# axiom_beta_interface_dummy_v0_13_r1_3.net
KiCad netlist of a schematic drawn in EAGLE
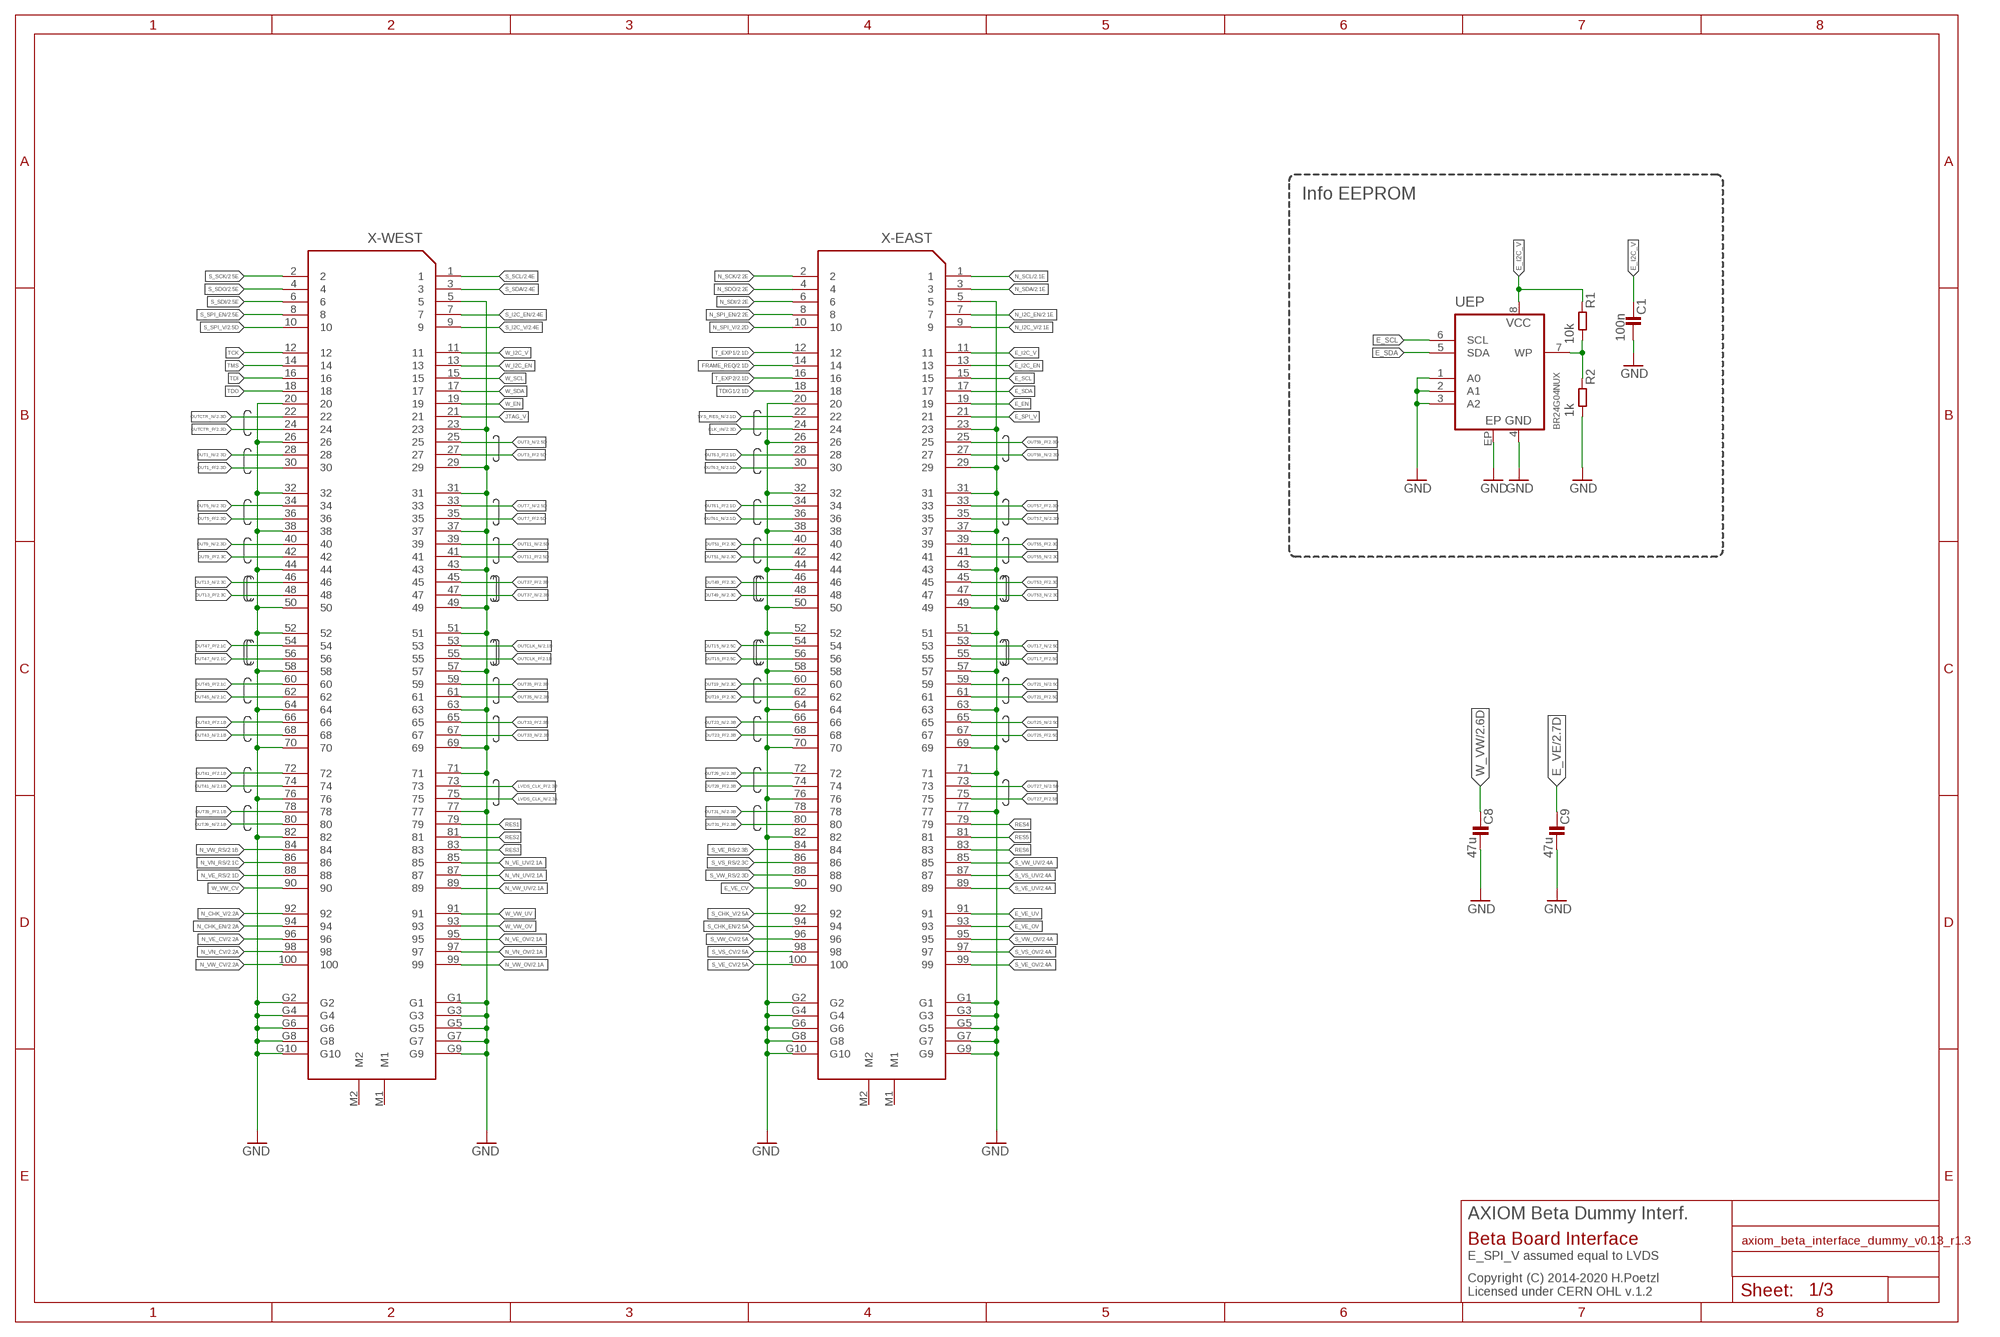
[diagram p0: schematic, sheet 1]
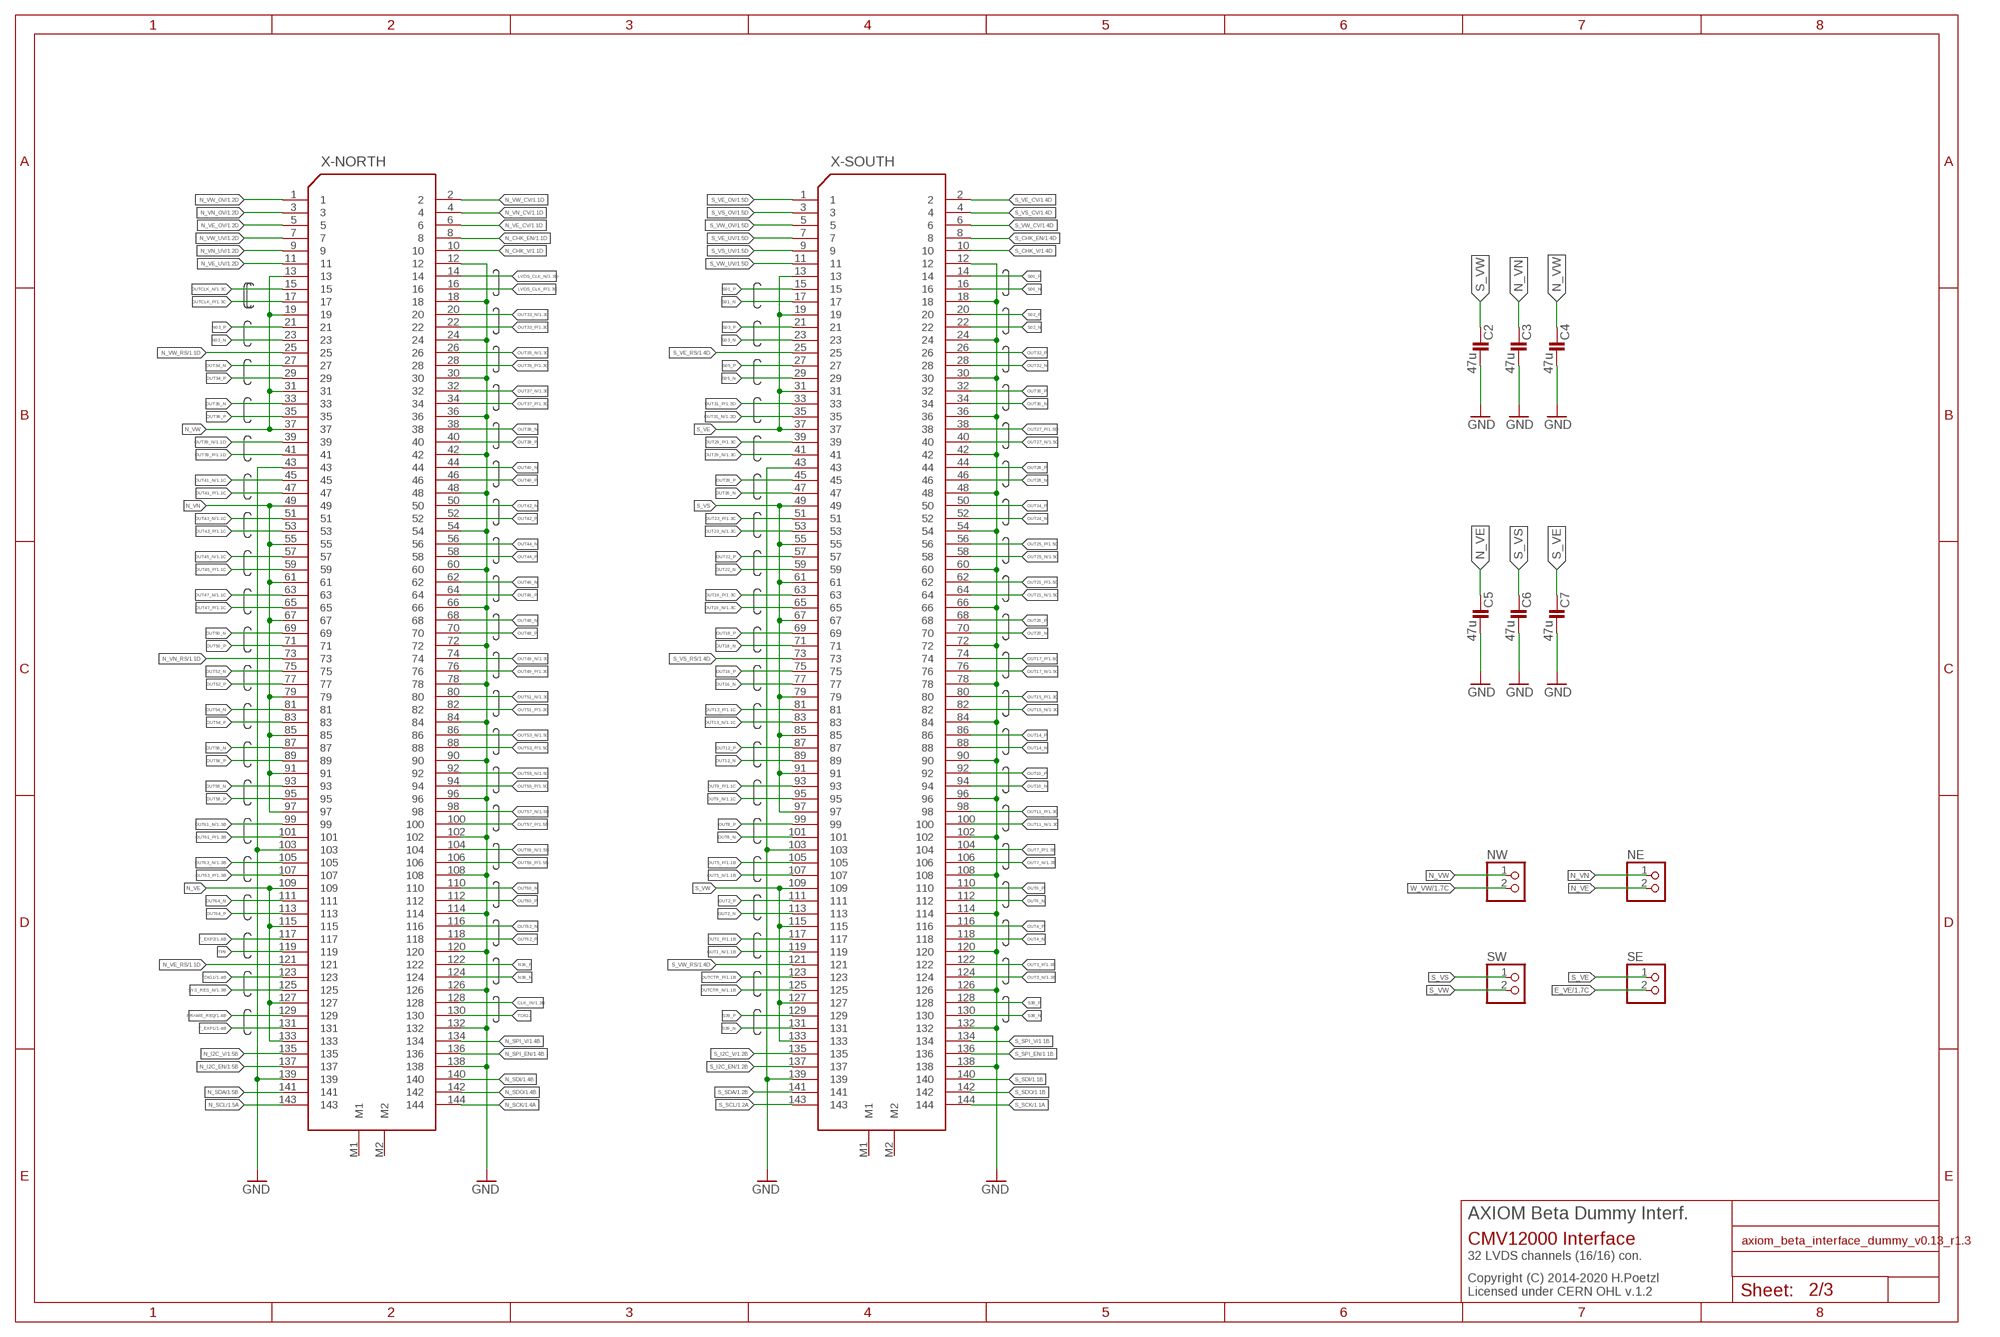
[diagram p1: schematic, sheet 2]
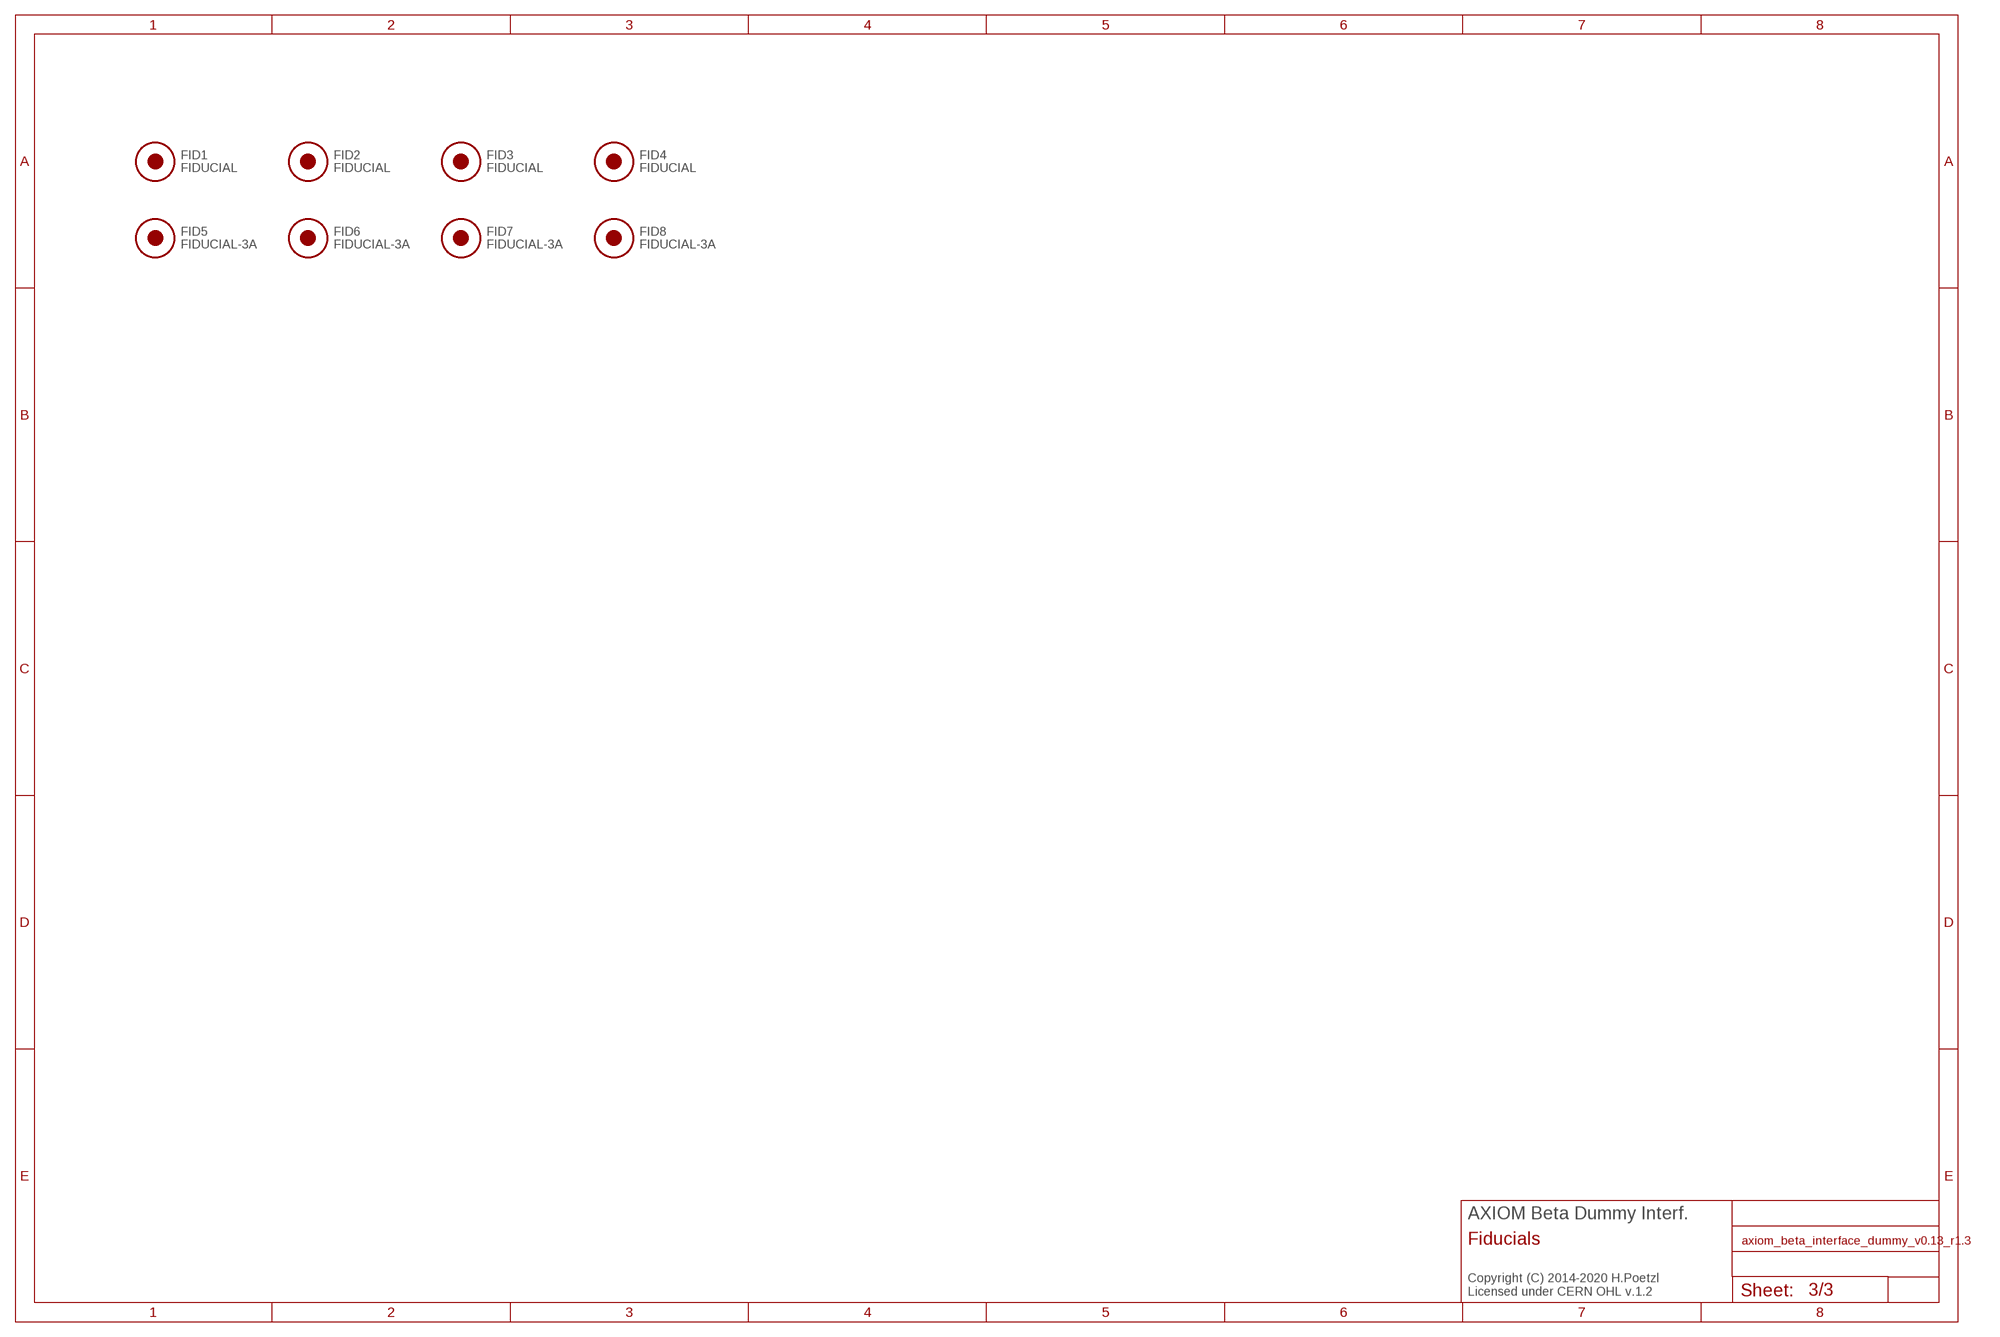
[diagram p2: schematic, sheet 3]

(export (version "E")
  (design (tool "Eeschema 10.0.6"))
  (components
    (comp (ref "FID1")
      (value "FIDUCIAL")
      (footprint "eagle-import:FID_ARROW")
      (libsource (lib "eagle-import") (part "FIDUCIAL"))
    )
    (comp (ref "FID2")
      (value "FIDUCIAL")
      (footprint "eagle-import:FID_ARROW")
      (libsource (lib "eagle-import") (part "FIDUCIAL"))
    )
    (comp (ref "FID3")
      (value "FIDUCIAL")
      (footprint "eagle-import:FID_ARROW")
      (libsource (lib "eagle-import") (part "FIDUCIAL"))
    )
    (comp (ref "FID4")
      (value "FIDUCIAL")
      (footprint "eagle-import:FID_ARROW")
      (libsource (lib "eagle-import") (part "FIDUCIAL"))
    )
    (comp (ref "FID5")
      (value "FIDUCIAL-3A")
      (footprint "eagle-import:FID_3ARROW")
      (libsource (lib "eagle-import") (part "FIDUCIAL-3A"))
    )
    (comp (ref "FID6")
      (value "FIDUCIAL-3A")
      (footprint "eagle-import:FID_3ARROW")
      (libsource (lib "eagle-import") (part "FIDUCIAL-3A"))
    )
    (comp (ref "FID7")
      (value "FIDUCIAL-3A")
      (footprint "eagle-import:FID_3ARROW")
      (libsource (lib "eagle-import") (part "FIDUCIAL-3A"))
    )
    (comp (ref "FID8")
      (value "FIDUCIAL-3A")
      (footprint "eagle-import:FID_3ARROW")
      (libsource (lib "eagle-import") (part "FIDUCIAL-3A"))
    )
    (comp (ref "C1")
      (value "100n")
      (footprint "eagle-import:0402-B")
      (libsource (lib "eagle-import") (part "C0402-B"))
    )
    (comp (ref "C8")
      (value "47u")
      (footprint "eagle-import:0805-B")
      (libsource (lib "eagle-import") (part "C0805-B"))
    )
    (comp (ref "C9")
      (value "47u")
      (footprint "eagle-import:0805-B")
      (libsource (lib "eagle-import") (part "C0805-B"))
    )
    (comp (ref "R1")
      (value "10k")
      (footprint "eagle-import:0402-B")
      (libsource (lib "eagle-import") (part "R0402-B"))
    )
    (comp (ref "R2")
      (value "1k")
      (footprint "eagle-import:0402-B")
      (libsource (lib "eagle-import") (part "R0402-B"))
    )
    (comp (ref "UEP")
      (value "BR24G04NUX")
      (footprint "eagle-import:DFN200X300X100-9N")
      (libsource (lib "eagle-import") (part "BR24G04NUX"))
    )
    (comp (ref "X-EAST")
      (value "FX10-100/10P")
      (footprint "eagle-import:FX10A-100P_10")
      (libsource (lib "eagle-import") (part "FX10-100/10P"))
    )
    (comp (ref "X-WEST")
      (value "FX10-100/10P")
      (footprint "eagle-import:FX10A-100P_10")
      (libsource (lib "eagle-import") (part "FX10-100/10P"))
    )
    (comp (ref "C2")
      (value "47u")
      (footprint "eagle-import:0805-B")
      (libsource (lib "eagle-import") (part "C0805-B"))
    )
    (comp (ref "C3")
      (value "47u")
      (footprint "eagle-import:0805-B")
      (libsource (lib "eagle-import") (part "C0805-B"))
    )
    (comp (ref "C4")
      (value "47u")
      (footprint "eagle-import:0805-B")
      (libsource (lib "eagle-import") (part "C0805-B"))
    )
    (comp (ref "C5")
      (value "47u")
      (footprint "eagle-import:0805-B")
      (libsource (lib "eagle-import") (part "C0805-B"))
    )
    (comp (ref "C6")
      (value "47u")
      (footprint "eagle-import:0805-B")
      (libsource (lib "eagle-import") (part "C0805-B"))
    )
    (comp (ref "C7")
      (value "47u")
      (footprint "eagle-import:0805-B")
      (libsource (lib "eagle-import") (part "C0805-B"))
    )
    (comp (ref "NE")
      (value "PINHD-1X02_2.54")
      (footprint "eagle-import:1X02")
      (libsource (lib "eagle-import") (part "PINHD-1X02_2.54"))
    )
    (comp (ref "NW")
      (value "PINHD-1X02_2.54")
      (footprint "eagle-import:1X02")
      (libsource (lib "eagle-import") (part "PINHD-1X02_2.54"))
    )
    (comp (ref "SE")
      (value "PINHD-1X02_2.54")
      (footprint "eagle-import:1X02")
      (libsource (lib "eagle-import") (part "PINHD-1X02_2.54"))
    )
    (comp (ref "SW")
      (value "PINHD-1X02_2.54")
      (footprint "eagle-import:1X02")
      (libsource (lib "eagle-import") (part "PINHD-1X02_2.54"))
    )
    (comp (ref "X-NORTH")
      (value "FX10-144S")
      (footprint "eagle-import:FX10A-144S")
      (libsource (lib "eagle-import") (part "FX10-144S"))
    )
    (comp (ref "X-SOUTH")
      (value "FX10-144S")
      (footprint "eagle-import:FX10A-144S")
      (libsource (lib "eagle-import") (part "FX10-144S"))
    )
  )
  (nets
    (net (code "1") (name "CLK_IN") (class "Default")
      (node (ref "X-EAST") (pin "24") (pinfunction "24_24") (pintype "bidirectional"))
      (node (ref "X-NORTH") (pin "128") (pinfunction "128_128") (pintype "bidirectional"))
    )
    (net (code "2") (name "E_EN") (class "Default")
      (node (ref "X-EAST") (pin "19") (pinfunction "19_19") (pintype "bidirectional"))
    )
    (net (code "3") (name "E_I2C_EN") (class "Default")
      (node (ref "X-EAST") (pin "13") (pinfunction "13_13") (pintype "bidirectional"))
    )
    (net (code "4") (name "E_I2C_V") (class "Default")
      (node (ref "C1") (pin "1") (pinfunction "1_1") (pintype "passive"))
      (node (ref "R1") (pin "1") (pinfunction "1_1") (pintype "passive"))
      (node (ref "UEP") (pin "8") (pinfunction "VCC_8") (pintype "power_in"))
      (node (ref "X-EAST") (pin "11") (pinfunction "11_11") (pintype "bidirectional"))
    )
    (net (code "5") (name "E_SCL") (class "Default")
      (node (ref "UEP") (pin "6") (pinfunction "SCL_6") (pintype "input"))
      (node (ref "X-EAST") (pin "15") (pinfunction "15_15") (pintype "bidirectional"))
    )
    (net (code "6") (name "E_SDA") (class "Default")
      (node (ref "UEP") (pin "5") (pinfunction "SDA_5") (pintype "bidirectional"))
      (node (ref "X-EAST") (pin "17") (pinfunction "17_17") (pintype "bidirectional"))
    )
    (net (code "7") (name "E_SPI_V") (class "Default")
      (node (ref "X-EAST") (pin "21") (pinfunction "21_21") (pintype "bidirectional"))
    )
    (net (code "8") (name "E_VE") (class "Default")
      (node (ref "C9") (pin "1") (pinfunction "1_1") (pintype "passive"))
      (node (ref "SE") (pin "2") (pinfunction "2_2") (pintype "passive"))
    )
    (net (code "9") (name "E_VE_CV") (class "Default")
      (node (ref "X-EAST") (pin "90") (pinfunction "90_90") (pintype "bidirectional"))
    )
    (net (code "10") (name "E_VE_OV") (class "Default")
      (node (ref "X-EAST") (pin "93") (pinfunction "93_93") (pintype "bidirectional"))
    )
    (net (code "11") (name "E_VE_UV") (class "Default")
      (node (ref "X-EAST") (pin "91") (pinfunction "91_91") (pintype "bidirectional"))
    )
    (net (code "12") (name "FRAME_REQ") (class "Default")
      (node (ref "X-EAST") (pin "14") (pinfunction "14_14") (pintype "bidirectional"))
      (node (ref "X-NORTH") (pin "129") (pinfunction "129_129") (pintype "bidirectional"))
    )
    (net (code "13") (name "GND") (class "Default")
      (node (ref "C1") (pin "2") (pinfunction "2_2") (pintype "passive"))
      (node (ref "C2") (pin "2") (pinfunction "2_2") (pintype "passive"))
      (node (ref "C3") (pin "2") (pinfunction "2_2") (pintype "passive"))
      (node (ref "C4") (pin "2") (pinfunction "2_2") (pintype "passive"))
      (node (ref "C5") (pin "2") (pinfunction "2_2") (pintype "passive"))
      (node (ref "C6") (pin "2") (pinfunction "2_2") (pintype "passive"))
      (node (ref "C7") (pin "2") (pinfunction "2_2") (pintype "passive"))
      (node (ref "C8") (pin "2") (pinfunction "2_2") (pintype "passive"))
      (node (ref "C9") (pin "2") (pinfunction "2_2") (pintype "passive"))
      (node (ref "R2") (pin "2") (pinfunction "2_2") (pintype "passive"))
      (node (ref "UEP") (pin "1") (pinfunction "A0_1") (pintype "input"))
      (node (ref "UEP") (pin "2") (pinfunction "A1_2") (pintype "input"))
      (node (ref "UEP") (pin "3") (pinfunction "A2_3") (pintype "input"))
      (node (ref "UEP") (pin "4") (pinfunction "GND_4") (pintype "passive"))
      (node (ref "UEP") (pin "EP") (pinfunction "EP_EP") (pintype "passive"))
      (node (ref "X-EAST") (pin "20") (pinfunction "20_20") (pintype "bidirectional"))
      (node (ref "X-EAST") (pin "23") (pinfunction "23_23") (pintype "bidirectional"))
      (node (ref "X-EAST") (pin "26") (pinfunction "26_26") (pintype "bidirectional"))
      (node (ref "X-EAST") (pin "29") (pinfunction "29_29") (pintype "bidirectional"))
      (node (ref "X-EAST") (pin "31") (pinfunction "31_31") (pintype "bidirectional"))
      (node (ref "X-EAST") (pin "32") (pinfunction "32_32") (pintype "bidirectional"))
      (node (ref "X-EAST") (pin "37") (pinfunction "37_37") (pintype "bidirectional"))
      (node (ref "X-EAST") (pin "38") (pinfunction "38_38") (pintype "bidirectional"))
      (node (ref "X-EAST") (pin "43") (pinfunction "43_43") (pintype "bidirectional"))
      (node (ref "X-EAST") (pin "44") (pinfunction "44_44") (pintype "bidirectional"))
      (node (ref "X-EAST") (pin "49") (pinfunction "49_49") (pintype "bidirectional"))
      (node (ref "X-EAST") (pin "5") (pinfunction "5_5") (pintype "bidirectional"))
      (node (ref "X-EAST") (pin "50") (pinfunction "50_50") (pintype "bidirectional"))
      (node (ref "X-EAST") (pin "51") (pinfunction "51_51") (pintype "bidirectional"))
      (node (ref "X-EAST") (pin "52") (pinfunction "52_52") (pintype "bidirectional"))
      (node (ref "X-EAST") (pin "57") (pinfunction "57_57") (pintype "bidirectional"))
      (node (ref "X-EAST") (pin "58") (pinfunction "58_58") (pintype "bidirectional"))
      (node (ref "X-EAST") (pin "63") (pinfunction "63_63") (pintype "bidirectional"))
      (node (ref "X-EAST") (pin "64") (pinfunction "64_64") (pintype "bidirectional"))
      (node (ref "X-EAST") (pin "69") (pinfunction "69_69") (pintype "bidirectional"))
      (node (ref "X-EAST") (pin "70") (pinfunction "70_70") (pintype "bidirectional"))
      (node (ref "X-EAST") (pin "71") (pinfunction "71_71") (pintype "bidirectional"))
      (node (ref "X-EAST") (pin "76") (pinfunction "76_76") (pintype "bidirectional"))
      (node (ref "X-EAST") (pin "77") (pinfunction "77_77") (pintype "bidirectional"))
      (node (ref "X-EAST") (pin "82") (pinfunction "82_82") (pintype "bidirectional"))
      (node (ref "X-EAST") (pin "G1") (pinfunction "G1_G1") (pintype "bidirectional"))
      (node (ref "X-EAST") (pin "G10") (pinfunction "G10_G10") (pintype "bidirectional"))
      (node (ref "X-EAST") (pin "G2") (pinfunction "G2_G2") (pintype "bidirectional"))
      (node (ref "X-EAST") (pin "G3") (pinfunction "G3_G3") (pintype "bidirectional"))
      (node (ref "X-EAST") (pin "G4") (pinfunction "G4_G4") (pintype "bidirectional"))
      (node (ref "X-EAST") (pin "G5") (pinfunction "G5_G5") (pintype "bidirectional"))
      (node (ref "X-EAST") (pin "G6") (pinfunction "G6_G6") (pintype "bidirectional"))
      (node (ref "X-EAST") (pin "G7") (pinfunction "G7_G7") (pintype "bidirectional"))
      (node (ref "X-EAST") (pin "G8") (pinfunction "G8_G8") (pintype "bidirectional"))
      (node (ref "X-EAST") (pin "G9") (pinfunction "G9_G9") (pintype "bidirectional"))
      (node (ref "X-NORTH") (pin "102") (pinfunction "102_102") (pintype "bidirectional"))
      (node (ref "X-NORTH") (pin "103") (pinfunction "103_103") (pintype "bidirectional"))
      (node (ref "X-NORTH") (pin "108") (pinfunction "108_108") (pintype "bidirectional"))
      (node (ref "X-NORTH") (pin "114") (pinfunction "114_114") (pintype "bidirectional"))
      (node (ref "X-NORTH") (pin "12") (pinfunction "12_12") (pintype "bidirectional"))
      (node (ref "X-NORTH") (pin "120") (pinfunction "120_120") (pintype "bidirectional"))
      (node (ref "X-NORTH") (pin "126") (pinfunction "126_126") (pintype "bidirectional"))
      (node (ref "X-NORTH") (pin "132") (pinfunction "132_132") (pintype "bidirectional"))
      (node (ref "X-NORTH") (pin "138") (pinfunction "138_138") (pintype "bidirectional"))
      (node (ref "X-NORTH") (pin "139") (pinfunction "139_139") (pintype "bidirectional"))
      (node (ref "X-NORTH") (pin "18") (pinfunction "18_18") (pintype "bidirectional"))
      (node (ref "X-NORTH") (pin "24") (pinfunction "24_24") (pintype "bidirectional"))
      (node (ref "X-NORTH") (pin "30") (pinfunction "30_30") (pintype "bidirectional"))
      (node (ref "X-NORTH") (pin "36") (pinfunction "36_36") (pintype "bidirectional"))
      (node (ref "X-NORTH") (pin "42") (pinfunction "42_42") (pintype "bidirectional"))
      (node (ref "X-NORTH") (pin "43") (pinfunction "43_43") (pintype "bidirectional"))
      (node (ref "X-NORTH") (pin "48") (pinfunction "48_48") (pintype "bidirectional"))
      (node (ref "X-NORTH") (pin "54") (pinfunction "54_54") (pintype "bidirectional"))
      (node (ref "X-NORTH") (pin "60") (pinfunction "60_60") (pintype "bidirectional"))
      (node (ref "X-NORTH") (pin "66") (pinfunction "66_66") (pintype "bidirectional"))
      (node (ref "X-NORTH") (pin "72") (pinfunction "72_72") (pintype "bidirectional"))
      (node (ref "X-NORTH") (pin "78") (pinfunction "78_78") (pintype "bidirectional"))
      (node (ref "X-NORTH") (pin "84") (pinfunction "84_84") (pintype "bidirectional"))
      (node (ref "X-NORTH") (pin "90") (pinfunction "90_90") (pintype "bidirectional"))
      (node (ref "X-NORTH") (pin "96") (pinfunction "96_96") (pintype "bidirectional"))
      (node (ref "X-SOUTH") (pin "102") (pinfunction "102_102") (pintype "bidirectional"))
      (node (ref "X-SOUTH") (pin "103") (pinfunction "103_103") (pintype "bidirectional"))
      (node (ref "X-SOUTH") (pin "108") (pinfunction "108_108") (pintype "bidirectional"))
      (node (ref "X-SOUTH") (pin "114") (pinfunction "114_114") (pintype "bidirectional"))
      (node (ref "X-SOUTH") (pin "12") (pinfunction "12_12") (pintype "bidirectional"))
      (node (ref "X-SOUTH") (pin "120") (pinfunction "120_120") (pintype "bidirectional"))
      (node (ref "X-SOUTH") (pin "126") (pinfunction "126_126") (pintype "bidirectional"))
      (node (ref "X-SOUTH") (pin "132") (pinfunction "132_132") (pintype "bidirectional"))
      (node (ref "X-SOUTH") (pin "138") (pinfunction "138_138") (pintype "bidirectional"))
      (node (ref "X-SOUTH") (pin "139") (pinfunction "139_139") (pintype "bidirectional"))
      (node (ref "X-SOUTH") (pin "18") (pinfunction "18_18") (pintype "bidirectional"))
      (node (ref "X-SOUTH") (pin "24") (pinfunction "24_24") (pintype "bidirectional"))
      (node (ref "X-SOUTH") (pin "30") (pinfunction "30_30") (pintype "bidirectional"))
      (node (ref "X-SOUTH") (pin "36") (pinfunction "36_36") (pintype "bidirectional"))
      (node (ref "X-SOUTH") (pin "42") (pinfunction "42_42") (pintype "bidirectional"))
      (node (ref "X-SOUTH") (pin "43") (pinfunction "43_43") (pintype "bidirectional"))
      (node (ref "X-SOUTH") (pin "48") (pinfunction "48_48") (pintype "bidirectional"))
      (node (ref "X-SOUTH") (pin "54") (pinfunction "54_54") (pintype "bidirectional"))
      (node (ref "X-SOUTH") (pin "60") (pinfunction "60_60") (pintype "bidirectional"))
      (node (ref "X-SOUTH") (pin "66") (pinfunction "66_66") (pintype "bidirectional"))
      (node (ref "X-SOUTH") (pin "72") (pinfunction "72_72") (pintype "bidirectional"))
      (node (ref "X-SOUTH") (pin "78") (pinfunction "78_78") (pintype "bidirectional"))
      (node (ref "X-SOUTH") (pin "84") (pinfunction "84_84") (pintype "bidirectional"))
      (node (ref "X-SOUTH") (pin "90") (pinfunction "90_90") (pintype "bidirectional"))
      (node (ref "X-SOUTH") (pin "96") (pinfunction "96_96") (pintype "bidirectional"))
      (node (ref "X-WEST") (pin "20") (pinfunction "20_20") (pintype "bidirectional"))
      (node (ref "X-WEST") (pin "23") (pinfunction "23_23") (pintype "bidirectional"))
      (node (ref "X-WEST") (pin "26") (pinfunction "26_26") (pintype "bidirectional"))
      (node (ref "X-WEST") (pin "29") (pinfunction "29_29") (pintype "bidirectional"))
      (node (ref "X-WEST") (pin "31") (pinfunction "31_31") (pintype "bidirectional"))
      (node (ref "X-WEST") (pin "32") (pinfunction "32_32") (pintype "bidirectional"))
      (node (ref "X-WEST") (pin "37") (pinfunction "37_37") (pintype "bidirectional"))
      (node (ref "X-WEST") (pin "38") (pinfunction "38_38") (pintype "bidirectional"))
      (node (ref "X-WEST") (pin "43") (pinfunction "43_43") (pintype "bidirectional"))
      (node (ref "X-WEST") (pin "44") (pinfunction "44_44") (pintype "bidirectional"))
      (node (ref "X-WEST") (pin "49") (pinfunction "49_49") (pintype "bidirectional"))
      (node (ref "X-WEST") (pin "5") (pinfunction "5_5") (pintype "bidirectional"))
      (node (ref "X-WEST") (pin "50") (pinfunction "50_50") (pintype "bidirectional"))
      (node (ref "X-WEST") (pin "51") (pinfunction "51_51") (pintype "bidirectional"))
      (node (ref "X-WEST") (pin "52") (pinfunction "52_52") (pintype "bidirectional"))
      (node (ref "X-WEST") (pin "57") (pinfunction "57_57") (pintype "bidirectional"))
      (node (ref "X-WEST") (pin "58") (pinfunction "58_58") (pintype "bidirectional"))
      (node (ref "X-WEST") (pin "63") (pinfunction "63_63") (pintype "bidirectional"))
      (node (ref "X-WEST") (pin "64") (pinfunction "64_64") (pintype "bidirectional"))
      (node (ref "X-WEST") (pin "69") (pinfunction "69_69") (pintype "bidirectional"))
      (node (ref "X-WEST") (pin "70") (pinfunction "70_70") (pintype "bidirectional"))
      (node (ref "X-WEST") (pin "71") (pinfunction "71_71") (pintype "bidirectional"))
      (node (ref "X-WEST") (pin "76") (pinfunction "76_76") (pintype "bidirectional"))
      (node (ref "X-WEST") (pin "77") (pinfunction "77_77") (pintype "bidirectional"))
      (node (ref "X-WEST") (pin "82") (pinfunction "82_82") (pintype "bidirectional"))
      (node (ref "X-WEST") (pin "G1") (pinfunction "G1_G1") (pintype "bidirectional"))
      (node (ref "X-WEST") (pin "G10") (pinfunction "G10_G10") (pintype "bidirectional"))
      (node (ref "X-WEST") (pin "G2") (pinfunction "G2_G2") (pintype "bidirectional"))
      (node (ref "X-WEST") (pin "G3") (pinfunction "G3_G3") (pintype "bidirectional"))
      (node (ref "X-WEST") (pin "G4") (pinfunction "G4_G4") (pintype "bidirectional"))
      (node (ref "X-WEST") (pin "G5") (pinfunction "G5_G5") (pintype "bidirectional"))
      (node (ref "X-WEST") (pin "G6") (pinfunction "G6_G6") (pintype "bidirectional"))
      (node (ref "X-WEST") (pin "G7") (pinfunction "G7_G7") (pintype "bidirectional"))
      (node (ref "X-WEST") (pin "G8") (pinfunction "G8_G8") (pintype "bidirectional"))
      (node (ref "X-WEST") (pin "G9") (pinfunction "G9_G9") (pintype "bidirectional"))
    )
    (net (code "14") (name "JTAG_V") (class "Default")
      (node (ref "X-WEST") (pin "21") (pinfunction "21_21") (pintype "bidirectional"))
    )
    (net (code "15") (name "LVDS_CLK_N") (class "Default")
      (node (ref "X-NORTH") (pin "14") (pinfunction "14_14") (pintype "bidirectional"))
      (node (ref "X-WEST") (pin "75") (pinfunction "75_75") (pintype "bidirectional"))
    )
    (net (code "16") (name "LVDS_CLK_P") (class "Default")
      (node (ref "X-NORTH") (pin "16") (pinfunction "16_16") (pintype "bidirectional"))
      (node (ref "X-WEST") (pin "73") (pinfunction "73_73") (pintype "bidirectional"))
    )
    (net (code "17") (name "N03_N") (class "Default")
      (node (ref "X-NORTH") (pin "23") (pinfunction "23_23") (pintype "bidirectional"))
    )
    (net (code "18") (name "N03_P") (class "Default")
      (node (ref "X-NORTH") (pin "21") (pinfunction "21_21") (pintype "bidirectional"))
    )
    (net (code "19") (name "N36_N") (class "Default")
      (node (ref "X-NORTH") (pin "124") (pinfunction "124_124") (pintype "bidirectional"))
    )
    (net (code "20") (name "N36_P") (class "Default")
      (node (ref "X-NORTH") (pin "122") (pinfunction "122_122") (pintype "bidirectional"))
    )
    (net (code "21") (name "N_CHK_EN") (class "Default")
      (node (ref "X-NORTH") (pin "8") (pinfunction "8_8") (pintype "bidirectional"))
      (node (ref "X-WEST") (pin "94") (pinfunction "94_94") (pintype "bidirectional"))
    )
    (net (code "22") (name "N_CHK_V") (class "Default")
      (node (ref "X-NORTH") (pin "10") (pinfunction "10_10") (pintype "bidirectional"))
      (node (ref "X-WEST") (pin "92") (pinfunction "92_92") (pintype "bidirectional"))
    )
    (net (code "23") (name "N_I2C_EN") (class "Default")
      (node (ref "X-EAST") (pin "7") (pinfunction "7_7") (pintype "bidirectional"))
      (node (ref "X-NORTH") (pin "137") (pinfunction "137_137") (pintype "bidirectional"))
    )
    (net (code "24") (name "N_I2C_V") (class "Default")
      (node (ref "X-EAST") (pin "9") (pinfunction "9_9") (pintype "bidirectional"))
      (node (ref "X-NORTH") (pin "135") (pinfunction "135_135") (pintype "bidirectional"))
    )
    (net (code "25") (name "N_SCK") (class "Default")
      (node (ref "X-EAST") (pin "2") (pinfunction "2_2") (pintype "bidirectional"))
      (node (ref "X-NORTH") (pin "144") (pinfunction "144_144") (pintype "bidirectional"))
    )
    (net (code "26") (name "N_SCL") (class "Default")
      (node (ref "X-EAST") (pin "1") (pinfunction "1_1") (pintype "bidirectional"))
      (node (ref "X-NORTH") (pin "143") (pinfunction "143_143") (pintype "bidirectional"))
    )
    (net (code "27") (name "N_SDA") (class "Default")
      (node (ref "X-EAST") (pin "3") (pinfunction "3_3") (pintype "bidirectional"))
      (node (ref "X-NORTH") (pin "141") (pinfunction "141_141") (pintype "bidirectional"))
    )
    (net (code "28") (name "N_SDI") (class "Default")
      (node (ref "X-EAST") (pin "6") (pinfunction "6_6") (pintype "bidirectional"))
      (node (ref "X-NORTH") (pin "140") (pinfunction "140_140") (pintype "bidirectional"))
    )
    (net (code "29") (name "N_SDO") (class "Default")
      (node (ref "X-EAST") (pin "4") (pinfunction "4_4") (pintype "bidirectional"))
      (node (ref "X-NORTH") (pin "142") (pinfunction "142_142") (pintype "bidirectional"))
    )
    (net (code "30") (name "N_SPI_EN") (class "Default")
      (node (ref "X-EAST") (pin "8") (pinfunction "8_8") (pintype "bidirectional"))
      (node (ref "X-NORTH") (pin "136") (pinfunction "136_136") (pintype "bidirectional"))
    )
    (net (code "31") (name "N_SPI_V") (class "Default")
      (node (ref "X-EAST") (pin "10") (pinfunction "10_10") (pintype "bidirectional"))
      (node (ref "X-NORTH") (pin "134") (pinfunction "134_134") (pintype "bidirectional"))
    )
    (net (code "32") (name "N_VE") (class "Default")
      (node (ref "C5") (pin "1") (pinfunction "1_1") (pintype "passive"))
      (node (ref "NE") (pin "2") (pinfunction "2_2") (pintype "passive"))
      (node (ref "X-NORTH") (pin "109") (pinfunction "109_109") (pintype "bidirectional"))
      (node (ref "X-NORTH") (pin "115") (pinfunction "115_115") (pintype "bidirectional"))
      (node (ref "X-NORTH") (pin "127") (pinfunction "127_127") (pintype "bidirectional"))
      (node (ref "X-NORTH") (pin "133") (pinfunction "133_133") (pintype "bidirectional"))
    )
    (net (code "33") (name "N_VE_CV") (class "Default")
      (node (ref "X-NORTH") (pin "6") (pinfunction "6_6") (pintype "bidirectional"))
      (node (ref "X-WEST") (pin "96") (pinfunction "96_96") (pintype "bidirectional"))
    )
    (net (code "34") (name "N_VE_OV") (class "Default")
      (node (ref "X-NORTH") (pin "5") (pinfunction "5_5") (pintype "bidirectional"))
      (node (ref "X-WEST") (pin "95") (pinfunction "95_95") (pintype "bidirectional"))
    )
    (net (code "35") (name "N_VE_RS") (class "Default")
      (node (ref "X-NORTH") (pin "121") (pinfunction "121_121") (pintype "bidirectional"))
      (node (ref "X-WEST") (pin "88") (pinfunction "88_88") (pintype "bidirectional"))
    )
    (net (code "36") (name "N_VE_UV") (class "Default")
      (node (ref "X-NORTH") (pin "11") (pinfunction "11_11") (pintype "bidirectional"))
      (node (ref "X-WEST") (pin "85") (pinfunction "85_85") (pintype "bidirectional"))
    )
    (net (code "37") (name "N_VN") (class "Default")
      (node (ref "C3") (pin "1") (pinfunction "1_1") (pintype "passive"))
      (node (ref "NE") (pin "1") (pinfunction "1_1") (pintype "passive"))
      (node (ref "X-NORTH") (pin "49") (pinfunction "49_49") (pintype "bidirectional"))
      (node (ref "X-NORTH") (pin "55") (pinfunction "55_55") (pintype "bidirectional"))
      (node (ref "X-NORTH") (pin "61") (pinfunction "61_61") (pintype "bidirectional"))
      (node (ref "X-NORTH") (pin "67") (pinfunction "67_67") (pintype "bidirectional"))
      (node (ref "X-NORTH") (pin "79") (pinfunction "79_79") (pintype "bidirectional"))
      (node (ref "X-NORTH") (pin "85") (pinfunction "85_85") (pintype "bidirectional"))
      (node (ref "X-NORTH") (pin "91") (pinfunction "91_91") (pintype "bidirectional"))
      (node (ref "X-NORTH") (pin "97") (pinfunction "97_97") (pintype "bidirectional"))
    )
    (net (code "38") (name "N_VN_CV") (class "Default")
      (node (ref "X-NORTH") (pin "4") (pinfunction "4_4") (pintype "bidirectional"))
      (node (ref "X-WEST") (pin "98") (pinfunction "98_98") (pintype "bidirectional"))
    )
    (net (code "39") (name "N_VN_OV") (class "Default")
      (node (ref "X-NORTH") (pin "3") (pinfunction "3_3") (pintype "bidirectional"))
      (node (ref "X-WEST") (pin "97") (pinfunction "97_97") (pintype "bidirectional"))
    )
    (net (code "40") (name "N_VN_RS") (class "Default")
      (node (ref "X-NORTH") (pin "73") (pinfunction "73_73") (pintype "bidirectional"))
      (node (ref "X-WEST") (pin "86") (pinfunction "86_86") (pintype "bidirectional"))
    )
    (net (code "41") (name "N_VN_UV") (class "Default")
      (node (ref "X-NORTH") (pin "9") (pinfunction "9_9") (pintype "bidirectional"))
      (node (ref "X-WEST") (pin "87") (pinfunction "87_87") (pintype "bidirectional"))
    )
    (net (code "42") (name "N_VW") (class "Default")
      (node (ref "C4") (pin "1") (pinfunction "1_1") (pintype "passive"))
      (node (ref "NW") (pin "1") (pinfunction "1_1") (pintype "passive"))
      (node (ref "X-NORTH") (pin "13") (pinfunction "13_13") (pintype "bidirectional"))
      (node (ref "X-NORTH") (pin "19") (pinfunction "19_19") (pintype "bidirectional"))
      (node (ref "X-NORTH") (pin "31") (pinfunction "31_31") (pintype "bidirectional"))
      (node (ref "X-NORTH") (pin "37") (pinfunction "37_37") (pintype "bidirectional"))
    )
    (net (code "43") (name "N_VW_CV") (class "Default")
      (node (ref "X-NORTH") (pin "2") (pinfunction "2_2") (pintype "bidirectional"))
      (node (ref "X-WEST") (pin "100") (pinfunction "100_100") (pintype "bidirectional"))
    )
    (net (code "44") (name "N_VW_OV") (class "Default")
      (node (ref "X-NORTH") (pin "1") (pinfunction "1_1") (pintype "bidirectional"))
      (node (ref "X-WEST") (pin "99") (pinfunction "99_99") (pintype "bidirectional"))
    )
    (net (code "45") (name "N_VW_RS") (class "Default")
      (node (ref "X-NORTH") (pin "25") (pinfunction "25_25") (pintype "bidirectional"))
      (node (ref "X-WEST") (pin "84") (pinfunction "84_84") (pintype "bidirectional"))
    )
    (net (code "46") (name "N_VW_UV") (class "Default")
      (node (ref "X-NORTH") (pin "7") (pinfunction "7_7") (pintype "bidirectional"))
      (node (ref "X-WEST") (pin "89") (pinfunction "89_89") (pintype "bidirectional"))
    )
    (net (code "47") (name "Net-(UEP-WP)") (class "Default")
      (node (ref "R1") (pin "2") (pinfunction "2_2") (pintype "passive"))
      (node (ref "R2") (pin "1") (pinfunction "1_1") (pintype "passive"))
      (node (ref "UEP") (pin "7") (pinfunction "WP_7") (pintype "input"))
    )
    (net (code "48") (name "OUT1_N") (class "Default")
      (node (ref "X-SOUTH") (pin "119") (pinfunction "119_119") (pintype "bidirectional"))
      (node (ref "X-WEST") (pin "28") (pinfunction "28_28") (pintype "bidirectional"))
    )
    (net (code "49") (name "OUT1_P") (class "Default")
      (node (ref "X-SOUTH") (pin "117") (pinfunction "117_117") (pintype "bidirectional"))
      (node (ref "X-WEST") (pin "30") (pinfunction "30_30") (pintype "bidirectional"))
    )
    (net (code "50") (name "OUT2_N") (class "Default")
      (node (ref "X-SOUTH") (pin "113") (pinfunction "113_113") (pintype "bidirectional"))
    )
    (net (code "51") (name "OUT2_P") (class "Default")
      (node (ref "X-SOUTH") (pin "111") (pinfunction "111_111") (pintype "bidirectional"))
    )
    (net (code "52") (name "OUT3_N") (class "Default")
      (node (ref "X-SOUTH") (pin "124") (pinfunction "124_124") (pintype "bidirectional"))
      (node (ref "X-WEST") (pin "25") (pinfunction "25_25") (pintype "bidirectional"))
    )
    (net (code "53") (name "OUT3_P") (class "Default")
      (node (ref "X-SOUTH") (pin "122") (pinfunction "122_122") (pintype "bidirectional"))
      (node (ref "X-WEST") (pin "27") (pinfunction "27_27") (pintype "bidirectional"))
    )
    (net (code "54") (name "OUT4_N") (class "Default")
      (node (ref "X-SOUTH") (pin "118") (pinfunction "118_118") (pintype "bidirectional"))
    )
    (net (code "55") (name "OUT4_P") (class "Default")
      (node (ref "X-SOUTH") (pin "116") (pinfunction "116_116") (pintype "bidirectional"))
    )
    (net (code "56") (name "OUT5_N") (class "Default")
      (node (ref "X-SOUTH") (pin "107") (pinfunction "107_107") (pintype "bidirectional"))
      (node (ref "X-WEST") (pin "34") (pinfunction "34_34") (pintype "bidirectional"))
    )
    (net (code "57") (name "OUT5_P") (class "Default")
      (node (ref "X-SOUTH") (pin "105") (pinfunction "105_105") (pintype "bidirectional"))
      (node (ref "X-WEST") (pin "36") (pinfunction "36_36") (pintype "bidirectional"))
    )
    (net (code "58") (name "OUT6_N") (class "Default")
      (node (ref "X-SOUTH") (pin "112") (pinfunction "112_112") (pintype "bidirectional"))
    )
    (net (code "59") (name "OUT6_P") (class "Default")
      (node (ref "X-SOUTH") (pin "110") (pinfunction "110_110") (pintype "bidirectional"))
    )
    (net (code "60") (name "OUT7_N") (class "Default")
      (node (ref "X-SOUTH") (pin "106") (pinfunction "106_106") (pintype "bidirectional"))
      (node (ref "X-WEST") (pin "33") (pinfunction "33_33") (pintype "bidirectional"))
    )
    (net (code "61") (name "OUT7_P") (class "Default")
      (node (ref "X-SOUTH") (pin "104") (pinfunction "104_104") (pintype "bidirectional"))
      (node (ref "X-WEST") (pin "35") (pinfunction "35_35") (pintype "bidirectional"))
    )
    (net (code "62") (name "OUT8_N") (class "Default")
      (node (ref "X-SOUTH") (pin "101") (pinfunction "101_101") (pintype "bidirectional"))
    )
    (net (code "63") (name "OUT8_P") (class "Default")
      (node (ref "X-SOUTH") (pin "99") (pinfunction "99_99") (pintype "bidirectional"))
    )
    (net (code "64") (name "OUT9_N") (class "Default")
      (node (ref "X-SOUTH") (pin "95") (pinfunction "95_95") (pintype "bidirectional"))
      (node (ref "X-WEST") (pin "40") (pinfunction "40_40") (pintype "bidirectional"))
    )
    (net (code "65") (name "OUT9_P") (class "Default")
      (node (ref "X-SOUTH") (pin "93") (pinfunction "93_93") (pintype "bidirectional"))
      (node (ref "X-WEST") (pin "42") (pinfunction "42_42") (pintype "bidirectional"))
    )
    (net (code "66") (name "OUT10_N") (class "Default")
      (node (ref "X-SOUTH") (pin "94") (pinfunction "94_94") (pintype "bidirectional"))
    )
    (net (code "67") (name "OUT10_P") (class "Default")
      (node (ref "X-SOUTH") (pin "92") (pinfunction "92_92") (pintype "bidirectional"))
    )
    (net (code "68") (name "OUT11_N") (class "Default")
      (node (ref "X-SOUTH") (pin "100") (pinfunction "100_100") (pintype "bidirectional"))
      (node (ref "X-WEST") (pin "39") (pinfunction "39_39") (pintype "bidirectional"))
    )
    (net (code "69") (name "OUT11_P") (class "Default")
      (node (ref "X-SOUTH") (pin "98") (pinfunction "98_98") (pintype "bidirectional"))
      (node (ref "X-WEST") (pin "41") (pinfunction "41_41") (pintype "bidirectional"))
    )
    (net (code "70") (name "OUT12_N") (class "Default")
      (node (ref "X-SOUTH") (pin "89") (pinfunction "89_89") (pintype "bidirectional"))
    )
    (net (code "71") (name "OUT12_P") (class "Default")
      (node (ref "X-SOUTH") (pin "87") (pinfunction "87_87") (pintype "bidirectional"))
    )
    (net (code "72") (name "OUT13_N") (class "Default")
      (node (ref "X-SOUTH") (pin "83") (pinfunction "83_83") (pintype "bidirectional"))
      (node (ref "X-WEST") (pin "46") (pinfunction "46_46") (pintype "bidirectional"))
    )
    (net (code "73") (name "OUT13_P") (class "Default")
      (node (ref "X-SOUTH") (pin "81") (pinfunction "81_81") (pintype "bidirectional"))
      (node (ref "X-WEST") (pin "48") (pinfunction "48_48") (pintype "bidirectional"))
    )
    (net (code "74") (name "OUT14_N") (class "Default")
      (node (ref "X-SOUTH") (pin "88") (pinfunction "88_88") (pintype "bidirectional"))
    )
    (net (code "75") (name "OUT14_P") (class "Default")
      (node (ref "X-SOUTH") (pin "86") (pinfunction "86_86") (pintype "bidirectional"))
    )
    (net (code "76") (name "OUT15_N") (class "Default")
      (node (ref "X-EAST") (pin "54") (pinfunction "54_54") (pintype "bidirectional"))
      (node (ref "X-SOUTH") (pin "82") (pinfunction "82_82") (pintype "bidirectional"))
    )
    (net (code "77") (name "OUT15_P") (class "Default")
      (node (ref "X-EAST") (pin "56") (pinfunction "56_56") (pintype "bidirectional"))
      (node (ref "X-SOUTH") (pin "80") (pinfunction "80_80") (pintype "bidirectional"))
    )
    (net (code "78") (name "OUT16_N") (class "Default")
      (node (ref "X-SOUTH") (pin "77") (pinfunction "77_77") (pintype "bidirectional"))
    )
    (net (code "79") (name "OUT16_P") (class "Default")
      (node (ref "X-SOUTH") (pin "75") (pinfunction "75_75") (pintype "bidirectional"))
    )
    (net (code "80") (name "OUT17_N") (class "Default")
      (node (ref "X-EAST") (pin "53") (pinfunction "53_53") (pintype "bidirectional"))
      (node (ref "X-SOUTH") (pin "76") (pinfunction "76_76") (pintype "bidirectional"))
    )
    (net (code "81") (name "OUT17_P") (class "Default")
      (node (ref "X-EAST") (pin "55") (pinfunction "55_55") (pintype "bidirectional"))
      (node (ref "X-SOUTH") (pin "74") (pinfunction "74_74") (pintype "bidirectional"))
    )
    (net (code "82") (name "OUT18_N") (class "Default")
      (node (ref "X-SOUTH") (pin "71") (pinfunction "71_71") (pintype "bidirectional"))
    )
    (net (code "83") (name "OUT18_P") (class "Default")
      (node (ref "X-SOUTH") (pin "69") (pinfunction "69_69") (pintype "bidirectional"))
    )
    (net (code "84") (name "OUT19_N") (class "Default")
      (node (ref "X-EAST") (pin "60") (pinfunction "60_60") (pintype "bidirectional"))
      (node (ref "X-SOUTH") (pin "65") (pinfunction "65_65") (pintype "bidirectional"))
    )
    (net (code "85") (name "OUT19_P") (class "Default")
      (node (ref "X-EAST") (pin "62") (pinfunction "62_62") (pintype "bidirectional"))
      (node (ref "X-SOUTH") (pin "63") (pinfunction "63_63") (pintype "bidirectional"))
    )
    (net (code "86") (name "OUT20_N") (class "Default")
      (node (ref "X-SOUTH") (pin "70") (pinfunction "70_70") (pintype "bidirectional"))
    )
    (net (code "87") (name "OUT20_P") (class "Default")
      (node (ref "X-SOUTH") (pin "68") (pinfunction "68_68") (pintype "bidirectional"))
    )
    (net (code "88") (name "OUT21_N") (class "Default")
      (node (ref "X-EAST") (pin "59") (pinfunction "59_59") (pintype "bidirectional"))
      (node (ref "X-SOUTH") (pin "64") (pinfunction "64_64") (pintype "bidirectional"))
    )
    (net (code "89") (name "OUT21_P") (class "Default")
      (node (ref "X-EAST") (pin "61") (pinfunction "61_61") (pintype "bidirectional"))
      (node (ref "X-SOUTH") (pin "62") (pinfunction "62_62") (pintype "bidirectional"))
    )
    (net (code "90") (name "OUT22_N") (class "Default")
      (node (ref "X-SOUTH") (pin "59") (pinfunction "59_59") (pintype "bidirectional"))
    )
    (net (code "91") (name "OUT22_P") (class "Default")
      (node (ref "X-SOUTH") (pin "57") (pinfunction "57_57") (pintype "bidirectional"))
    )
    (net (code "92") (name "OUT23_N") (class "Default")
      (node (ref "X-EAST") (pin "66") (pinfunction "66_66") (pintype "bidirectional"))
      (node (ref "X-SOUTH") (pin "53") (pinfunction "53_53") (pintype "bidirectional"))
    )
    (net (code "93") (name "OUT23_P") (class "Default")
      (node (ref "X-EAST") (pin "68") (pinfunction "68_68") (pintype "bidirectional"))
      (node (ref "X-SOUTH") (pin "51") (pinfunction "51_51") (pintype "bidirectional"))
    )
    (net (code "94") (name "OUT24_N") (class "Default")
      (node (ref "X-SOUTH") (pin "52") (pinfunction "52_52") (pintype "bidirectional"))
    )
    (net (code "95") (name "OUT24_P") (class "Default")
      (node (ref "X-SOUTH") (pin "50") (pinfunction "50_50") (pintype "bidirectional"))
    )
    (net (code "96") (name "OUT25_N") (class "Default")
      (node (ref "X-EAST") (pin "65") (pinfunction "65_65") (pintype "bidirectional"))
      (node (ref "X-SOUTH") (pin "58") (pinfunction "58_58") (pintype "bidirectional"))
    )
    (net (code "97") (name "OUT25_P") (class "Default")
      (node (ref "X-EAST") (pin "67") (pinfunction "67_67") (pintype "bidirectional"))
      (node (ref "X-SOUTH") (pin "56") (pinfunction "56_56") (pintype "bidirectional"))
    )
    (net (code "98") (name "OUT26_N") (class "Default")
      (node (ref "X-SOUTH") (pin "47") (pinfunction "47_47") (pintype "bidirectional"))
    )
    (net (code "99") (name "OUT26_P") (class "Default")
      (node (ref "X-SOUTH") (pin "45") (pinfunction "45_45") (pintype "bidirectional"))
    )
    (net (code "100") (name "OUT27_N") (class "Default")
      (node (ref "X-EAST") (pin "73") (pinfunction "73_73") (pintype "bidirectional"))
      (node (ref "X-SOUTH") (pin "40") (pinfunction "40_40") (pintype "bidirectional"))
    )
    (net (code "101") (name "OUT27_P") (class "Default")
      (node (ref "X-EAST") (pin "75") (pinfunction "75_75") (pintype "bidirectional"))
      (node (ref "X-SOUTH") (pin "38") (pinfunction "38_38") (pintype "bidirectional"))
    )
    (net (code "102") (name "OUT28_N") (class "Default")
      (node (ref "X-SOUTH") (pin "46") (pinfunction "46_46") (pintype "bidirectional"))
    )
    (net (code "103") (name "OUT28_P") (class "Default")
      (node (ref "X-SOUTH") (pin "44") (pinfunction "44_44") (pintype "bidirectional"))
    )
    (net (code "104") (name "OUT29_N") (class "Default")
      (node (ref "X-EAST") (pin "72") (pinfunction "72_72") (pintype "bidirectional"))
      (node (ref "X-SOUTH") (pin "41") (pinfunction "41_41") (pintype "bidirectional"))
    )
    (net (code "105") (name "OUT29_P") (class "Default")
      (node (ref "X-EAST") (pin "74") (pinfunction "74_74") (pintype "bidirectional"))
      (node (ref "X-SOUTH") (pin "39") (pinfunction "39_39") (pintype "bidirectional"))
    )
    (net (code "106") (name "OUT30_N") (class "Default")
      (node (ref "X-SOUTH") (pin "34") (pinfunction "34_34") (pintype "bidirectional"))
    )
    (net (code "107") (name "OUT30_P") (class "Default")
      (node (ref "X-SOUTH") (pin "32") (pinfunction "32_32") (pintype "bidirectional"))
    )
    (net (code "108") (name "OUT31_N") (class "Default")
      (node (ref "X-EAST") (pin "78") (pinfunction "78_78") (pintype "bidirectional"))
      (node (ref "X-SOUTH") (pin "35") (pinfunction "35_35") (pintype "bidirectional"))
    )
    (net (code "109") (name "OUT31_P") (class "Default")
      (node (ref "X-EAST") (pin "80") (pinfunction "80_80") (pintype "bidirectional"))
      (node (ref "X-SOUTH") (pin "33") (pinfunction "33_33") (pintype "bidirectional"))
    )
    (net (code "110") (name "OUT32_N") (class "Default")
      (node (ref "X-SOUTH") (pin "28") (pinfunction "28_28") (pintype "bidirectional"))
    )
    (net (code "111") (name "OUT32_P") (class "Default")
      (node (ref "X-SOUTH") (pin "26") (pinfunction "26_26") (pintype "bidirectional"))
    )
    (net (code "112") (name "OUT33_N") (class "Default")
      (node (ref "X-NORTH") (pin "20") (pinfunction "20_20") (pintype "bidirectional"))
      (node (ref "X-WEST") (pin "67") (pinfunction "67_67") (pintype "bidirectional"))
    )
    (net (code "113") (name "OUT33_P") (class "Default")
      (node (ref "X-NORTH") (pin "22") (pinfunction "22_22") (pintype "bidirectional"))
      (node (ref "X-WEST") (pin "65") (pinfunction "65_65") (pintype "bidirectional"))
    )
    (net (code "114") (name "OUT34_N") (class "Default")
      (node (ref "X-NORTH") (pin "27") (pinfunction "27_27") (pintype "bidirectional"))
    )
    (net (code "115") (name "OUT34_P") (class "Default")
      (node (ref "X-NORTH") (pin "29") (pinfunction "29_29") (pintype "bidirectional"))
    )
    (net (code "116") (name "OUT35_N") (class "Default")
      (node (ref "X-NORTH") (pin "26") (pinfunction "26_26") (pintype "bidirectional"))
      (node (ref "X-WEST") (pin "61") (pinfunction "61_61") (pintype "bidirectional"))
    )
    (net (code "117") (name "OUT35_P") (class "Default")
      (node (ref "X-NORTH") (pin "28") (pinfunction "28_28") (pintype "bidirectional"))
      (node (ref "X-WEST") (pin "59") (pinfunction "59_59") (pintype "bidirectional"))
    )
    (net (code "118") (name "OUT36_N") (class "Default")
      (node (ref "X-NORTH") (pin "33") (pinfunction "33_33") (pintype "bidirectional"))
    )
    (net (code "119") (name "OUT36_P") (class "Default")
      (node (ref "X-NORTH") (pin "35") (pinfunction "35_35") (pintype "bidirectional"))
    )
    (net (code "120") (name "OUT37_N") (class "Default")
      (node (ref "X-NORTH") (pin "32") (pinfunction "32_32") (pintype "bidirectional"))
      (node (ref "X-WEST") (pin "47") (pinfunction "47_47") (pintype "bidirectional"))
    )
    (net (code "121") (name "OUT37_P") (class "Default")
      (node (ref "X-NORTH") (pin "34") (pinfunction "34_34") (pintype "bidirectional"))
      (node (ref "X-WEST") (pin "45") (pinfunction "45_45") (pintype "bidirectional"))
    )
    (net (code "122") (name "OUT38_N") (class "Default")
      (node (ref "X-NORTH") (pin "38") (pinfunction "38_38") (pintype "bidirectional"))
    )
    (net (code "123") (name "OUT38_P") (class "Default")
      (node (ref "X-NORTH") (pin "40") (pinfunction "40_40") (pintype "bidirectional"))
    )
    (net (code "124") (name "OUT39_N") (class "Default")
      (node (ref "X-NORTH") (pin "39") (pinfunction "39_39") (pintype "bidirectional"))
      (node (ref "X-WEST") (pin "80") (pinfunction "80_80") (pintype "bidirectional"))
    )
    (net (code "125") (name "OUT39_P") (class "Default")
      (node (ref "X-NORTH") (pin "41") (pinfunction "41_41") (pintype "bidirectional"))
      (node (ref "X-WEST") (pin "78") (pinfunction "78_78") (pintype "bidirectional"))
    )
    (net (code "126") (name "OUT40_N") (class "Default")
      (node (ref "X-NORTH") (pin "44") (pinfunction "44_44") (pintype "bidirectional"))
    )
    (net (code "127") (name "OUT40_P") (class "Default")
      (node (ref "X-NORTH") (pin "46") (pinfunction "46_46") (pintype "bidirectional"))
    )
    (net (code "128") (name "OUT41_N") (class "Default")
      (node (ref "X-NORTH") (pin "45") (pinfunction "45_45") (pintype "bidirectional"))
      (node (ref "X-WEST") (pin "74") (pinfunction "74_74") (pintype "bidirectional"))
    )
    (net (code "129") (name "OUT41_P") (class "Default")
      (node (ref "X-NORTH") (pin "47") (pinfunction "47_47") (pintype "bidirectional"))
      (node (ref "X-WEST") (pin "72") (pinfunction "72_72") (pintype "bidirectional"))
    )
    (net (code "130") (name "OUT42_N") (class "Default")
      (node (ref "X-NORTH") (pin "50") (pinfunction "50_50") (pintype "bidirectional"))
    )
    (net (code "131") (name "OUT42_P") (class "Default")
      (node (ref "X-NORTH") (pin "52") (pinfunction "52_52") (pintype "bidirectional"))
    )
    (net (code "132") (name "OUT43_N") (class "Default")
      (node (ref "X-NORTH") (pin "51") (pinfunction "51_51") (pintype "bidirectional"))
      (node (ref "X-WEST") (pin "68") (pinfunction "68_68") (pintype "bidirectional"))
    )
    (net (code "133") (name "OUT43_P") (class "Default")
      (node (ref "X-NORTH") (pin "53") (pinfunction "53_53") (pintype "bidirectional"))
      (node (ref "X-WEST") (pin "66") (pinfunction "66_66") (pintype "bidirectional"))
    )
    (net (code "134") (name "OUT44_N") (class "Default")
      (node (ref "X-NORTH") (pin "56") (pinfunction "56_56") (pintype "bidirectional"))
    )
    (net (code "135") (name "OUT44_P") (class "Default")
      (node (ref "X-NORTH") (pin "58") (pinfunction "58_58") (pintype "bidirectional"))
    )
    (net (code "136") (name "OUT45_N") (class "Default")
      (node (ref "X-NORTH") (pin "57") (pinfunction "57_57") (pintype "bidirectional"))
      (node (ref "X-WEST") (pin "62") (pinfunction "62_62") (pintype "bidirectional"))
    )
    (net (code "137") (name "OUT45_P") (class "Default")
      (node (ref "X-NORTH") (pin "59") (pinfunction "59_59") (pintype "bidirectional"))
      (node (ref "X-WEST") (pin "60") (pinfunction "60_60") (pintype "bidirectional"))
    )
    (net (code "138") (name "OUT46_N") (class "Default")
      (node (ref "X-NORTH") (pin "62") (pinfunction "62_62") (pintype "bidirectional"))
    )
    (net (code "139") (name "OUT46_P") (class "Default")
      (node (ref "X-NORTH") (pin "64") (pinfunction "64_64") (pintype "bidirectional"))
    )
    (net (code "140") (name "OUT47_N") (class "Default")
      (node (ref "X-NORTH") (pin "63") (pinfunction "63_63") (pintype "bidirectional"))
      (node (ref "X-WEST") (pin "56") (pinfunction "56_56") (pintype "bidirectional"))
    )
    (net (code "141") (name "OUT47_P") (class "Default")
      (node (ref "X-NORTH") (pin "65") (pinfunction "65_65") (pintype "bidirectional"))
      (node (ref "X-WEST") (pin "54") (pinfunction "54_54") (pintype "bidirectional"))
    )
    (net (code "142") (name "OUT48_N") (class "Default")
      (node (ref "X-NORTH") (pin "68") (pinfunction "68_68") (pintype "bidirectional"))
    )
    (net (code "143") (name "OUT48_P") (class "Default")
      (node (ref "X-NORTH") (pin "70") (pinfunction "70_70") (pintype "bidirectional"))
    )
    (net (code "144") (name "OUT49_N") (class "Default")
      (node (ref "X-EAST") (pin "48") (pinfunction "48_48") (pintype "bidirectional"))
      (node (ref "X-NORTH") (pin "74") (pinfunction "74_74") (pintype "bidirectional"))
    )
    (net (code "145") (name "OUT49_P") (class "Default")
      (node (ref "X-EAST") (pin "46") (pinfunction "46_46") (pintype "bidirectional"))
      (node (ref "X-NORTH") (pin "76") (pinfunction "76_76") (pintype "bidirectional"))
    )
    (net (code "146") (name "OUT50_N") (class "Default")
      (node (ref "X-NORTH") (pin "69") (pinfunction "69_69") (pintype "bidirectional"))
    )
    (net (code "147") (name "OUT50_P") (class "Default")
      (node (ref "X-NORTH") (pin "71") (pinfunction "71_71") (pintype "bidirectional"))
    )
    (net (code "148") (name "OUT51_N") (class "Default")
      (node (ref "X-EAST") (pin "42") (pinfunction "42_42") (pintype "bidirectional"))
      (node (ref "X-NORTH") (pin "80") (pinfunction "80_80") (pintype "bidirectional"))
    )
    (net (code "149") (name "OUT51_P") (class "Default")
      (node (ref "X-EAST") (pin "40") (pinfunction "40_40") (pintype "bidirectional"))
      (node (ref "X-NORTH") (pin "82") (pinfunction "82_82") (pintype "bidirectional"))
    )
    (net (code "150") (name "OUT52_N") (class "Default")
      (node (ref "X-NORTH") (pin "75") (pinfunction "75_75") (pintype "bidirectional"))
    )
    (net (code "151") (name "OUT52_P") (class "Default")
      (node (ref "X-NORTH") (pin "77") (pinfunction "77_77") (pintype "bidirectional"))
    )
    (net (code "152") (name "OUT53_N") (class "Default")
      (node (ref "X-EAST") (pin "47") (pinfunction "47_47") (pintype "bidirectional"))
      (node (ref "X-NORTH") (pin "86") (pinfunction "86_86") (pintype "bidirectional"))
    )
    (net (code "153") (name "OUT53_P") (class "Default")
      (node (ref "X-EAST") (pin "45") (pinfunction "45_45") (pintype "bidirectional"))
      (node (ref "X-NORTH") (pin "88") (pinfunction "88_88") (pintype "bidirectional"))
    )
    (net (code "154") (name "OUT54_N") (class "Default")
      (node (ref "X-NORTH") (pin "81") (pinfunction "81_81") (pintype "bidirectional"))
    )
    (net (code "155") (name "OUT54_P") (class "Default")
      (node (ref "X-NORTH") (pin "83") (pinfunction "83_83") (pintype "bidirectional"))
    )
    (net (code "156") (name "OUT55_N") (class "Default")
      (node (ref "X-EAST") (pin "41") (pinfunction "41_41") (pintype "bidirectional"))
      (node (ref "X-NORTH") (pin "92") (pinfunction "92_92") (pintype "bidirectional"))
    )
    (net (code "157") (name "OUT55_P") (class "Default")
      (node (ref "X-EAST") (pin "39") (pinfunction "39_39") (pintype "bidirectional"))
      (node (ref "X-NORTH") (pin "94") (pinfunction "94_94") (pintype "bidirectional"))
    )
    (net (code "158") (name "OUT56_N") (class "Default")
      (node (ref "X-NORTH") (pin "87") (pinfunction "87_87") (pintype "bidirectional"))
    )
    (net (code "159") (name "OUT56_P") (class "Default")
      (node (ref "X-NORTH") (pin "89") (pinfunction "89_89") (pintype "bidirectional"))
    )
    (net (code "160") (name "OUT57_N") (class "Default")
      (node (ref "X-EAST") (pin "35") (pinfunction "35_35") (pintype "bidirectional"))
      (node (ref "X-NORTH") (pin "98") (pinfunction "98_98") (pintype "bidirectional"))
    )
    (net (code "161") (name "OUT57_P") (class "Default")
      (node (ref "X-EAST") (pin "33") (pinfunction "33_33") (pintype "bidirectional"))
      (node (ref "X-NORTH") (pin "100") (pinfunction "100_100") (pintype "bidirectional"))
    )
    (net (code "162") (name "OUT58_N") (class "Default")
      (node (ref "X-NORTH") (pin "93") (pinfunction "93_93") (pintype "bidirectional"))
    )
    (net (code "163") (name "OUT58_P") (class "Default")
      (node (ref "X-NORTH") (pin "95") (pinfunction "95_95") (pintype "bidirectional"))
    )
    (net (code "164") (name "OUT59_N") (class "Default")
      (node (ref "X-EAST") (pin "27") (pinfunction "27_27") (pintype "bidirectional"))
      (node (ref "X-NORTH") (pin "104") (pinfunction "104_104") (pintype "bidirectional"))
    )
    (net (code "165") (name "OUT59_P") (class "Default")
      (node (ref "X-EAST") (pin "25") (pinfunction "25_25") (pintype "bidirectional"))
      (node (ref "X-NORTH") (pin "106") (pinfunction "106_106") (pintype "bidirectional"))
    )
    (net (code "166") (name "OUT60_N") (class "Default")
      (node (ref "X-NORTH") (pin "110") (pinfunction "110_110") (pintype "bidirectional"))
    )
    (net (code "167") (name "OUT60_P") (class "Default")
      (node (ref "X-NORTH") (pin "112") (pinfunction "112_112") (pintype "bidirectional"))
    )
    (net (code "168") (name "OUT61_N") (class "Default")
      (node (ref "X-EAST") (pin "36") (pinfunction "36_36") (pintype "bidirectional"))
      (node (ref "X-NORTH") (pin "99") (pinfunction "99_99") (pintype "bidirectional"))
    )
    (net (code "169") (name "OUT61_P") (class "Default")
      (node (ref "X-EAST") (pin "34") (pinfunction "34_34") (pintype "bidirectional"))
      (node (ref "X-NORTH") (pin "101") (pinfunction "101_101") (pintype "bidirectional"))
    )
    (net (code "170") (name "OUT62_N") (class "Default")
      (node (ref "X-NORTH") (pin "116") (pinfunction "116_116") (pintype "bidirectional"))
    )
    (net (code "171") (name "OUT62_P") (class "Default")
      (node (ref "X-NORTH") (pin "118") (pinfunction "118_118") (pintype "bidirectional"))
    )
    (net (code "172") (name "OUT63_N") (class "Default")
      (node (ref "X-EAST") (pin "30") (pinfunction "30_30") (pintype "bidirectional"))
      (node (ref "X-NORTH") (pin "105") (pinfunction "105_105") (pintype "bidirectional"))
    )
    (net (code "173") (name "OUT63_P") (class "Default")
      (node (ref "X-EAST") (pin "28") (pinfunction "28_28") (pintype "bidirectional"))
      (node (ref "X-NORTH") (pin "107") (pinfunction "107_107") (pintype "bidirectional"))
    )
    (net (code "174") (name "OUT64_N") (class "Default")
      (node (ref "X-NORTH") (pin "111") (pinfunction "111_111") (pintype "bidirectional"))
    )
    (net (code "175") (name "OUT64_P") (class "Default")
      (node (ref "X-NORTH") (pin "113") (pinfunction "113_113") (pintype "bidirectional"))
    )
    (net (code "176") (name "OUTCLK_N") (class "Default")
      (node (ref "X-NORTH") (pin "15") (pinfunction "15_15") (pintype "bidirectional"))
      (node (ref "X-WEST") (pin "53") (pinfunction "53_53") (pintype "bidirectional"))
    )
    (net (code "177") (name "OUTCLK_P") (class "Default")
      (node (ref "X-NORTH") (pin "17") (pinfunction "17_17") (pintype "bidirectional"))
      (node (ref "X-WEST") (pin "55") (pinfunction "55_55") (pintype "bidirectional"))
    )
    (net (code "178") (name "OUTCTR_N") (class "Default")
      (node (ref "X-SOUTH") (pin "125") (pinfunction "125_125") (pintype "bidirectional"))
      (node (ref "X-WEST") (pin "22") (pinfunction "22_22") (pintype "bidirectional"))
    )
    (net (code "179") (name "OUTCTR_P") (class "Default")
      (node (ref "X-SOUTH") (pin "123") (pinfunction "123_123") (pintype "bidirectional"))
      (node (ref "X-WEST") (pin "24") (pinfunction "24_24") (pintype "bidirectional"))
    )
    (net (code "180") (name "RES1") (class "Default")
      (node (ref "X-WEST") (pin "79") (pinfunction "79_79") (pintype "bidirectional"))
    )
    (net (code "181") (name "RES2") (class "Default")
      (node (ref "X-WEST") (pin "81") (pinfunction "81_81") (pintype "bidirectional"))
    )
    (net (code "182") (name "RES3") (class "Default")
      (node (ref "X-WEST") (pin "83") (pinfunction "83_83") (pintype "bidirectional"))
    )
    (net (code "183") (name "RES4") (class "Default")
      (node (ref "X-EAST") (pin "79") (pinfunction "79_79") (pintype "bidirectional"))
    )
    (net (code "184") (name "RES5") (class "Default")
      (node (ref "X-EAST") (pin "81") (pinfunction "81_81") (pintype "bidirectional"))
    )
    (net (code "185") (name "RES6") (class "Default")
      (node (ref "X-EAST") (pin "83") (pinfunction "83_83") (pintype "bidirectional"))
    )
    (net (code "186") (name "S00_N") (class "Default")
      (node (ref "X-SOUTH") (pin "16") (pinfunction "16_16") (pintype "bidirectional"))
    )
    (net (code "187") (name "S00_P") (class "Default")
      (node (ref "X-SOUTH") (pin "14") (pinfunction "14_14") (pintype "bidirectional"))
    )
    (net (code "188") (name "S01_N") (class "Default")
      (node (ref "X-SOUTH") (pin "17") (pinfunction "17_17") (pintype "bidirectional"))
    )
    (net (code "189") (name "S01_P") (class "Default")
      (node (ref "X-SOUTH") (pin "15") (pinfunction "15_15") (pintype "bidirectional"))
    )
    (net (code "190") (name "S02_N") (class "Default")
      (node (ref "X-SOUTH") (pin "22") (pinfunction "22_22") (pintype "bidirectional"))
    )
    (net (code "191") (name "S02_P") (class "Default")
      (node (ref "X-SOUTH") (pin "20") (pinfunction "20_20") (pintype "bidirectional"))
    )
    (net (code "192") (name "S03_N") (class "Default")
      (node (ref "X-SOUTH") (pin "23") (pinfunction "23_23") (pintype "bidirectional"))
    )
    (net (code "193") (name "S03_P") (class "Default")
      (node (ref "X-SOUTH") (pin "21") (pinfunction "21_21") (pintype "bidirectional"))
    )
    (net (code "194") (name "S05_N") (class "Default")
      (node (ref "X-SOUTH") (pin "29") (pinfunction "29_29") (pintype "bidirectional"))
    )
    (net (code "195") (name "S05_P") (class "Default")
      (node (ref "X-SOUTH") (pin "27") (pinfunction "27_27") (pintype "bidirectional"))
    )
    (net (code "196") (name "S38_N") (class "Default")
      (node (ref "X-SOUTH") (pin "130") (pinfunction "130_130") (pintype "bidirectional"))
    )
    (net (code "197") (name "S38_P") (class "Default")
      (node (ref "X-SOUTH") (pin "128") (pinfunction "128_128") (pintype "bidirectional"))
    )
    (net (code "198") (name "S39_N") (class "Default")
      (node (ref "X-SOUTH") (pin "131") (pinfunction "131_131") (pintype "bidirectional"))
    )
    (net (code "199") (name "S39_P") (class "Default")
      (node (ref "X-SOUTH") (pin "129") (pinfunction "129_129") (pintype "bidirectional"))
    )
    (net (code "200") (name "SYS_RES_N") (class "Default")
      (node (ref "X-EAST") (pin "22") (pinfunction "22_22") (pintype "bidirectional"))
      (node (ref "X-NORTH") (pin "125") (pinfunction "125_125") (pintype "bidirectional"))
    )
    (net (code "201") (name "S_CHK_EN") (class "Default")
      (node (ref "X-EAST") (pin "94") (pinfunction "94_94") (pintype "bidirectional"))
      (node (ref "X-SOUTH") (pin "8") (pinfunction "8_8") (pintype "bidirectional"))
    )
    (net (code "202") (name "S_CHK_V") (class "Default")
      (node (ref "X-EAST") (pin "92") (pinfunction "92_92") (pintype "bidirectional"))
      (node (ref "X-SOUTH") (pin "10") (pinfunction "10_10") (pintype "bidirectional"))
    )
    (net (code "203") (name "S_I2C_EN") (class "Default")
      (node (ref "X-SOUTH") (pin "137") (pinfunction "137_137") (pintype "bidirectional"))
      (node (ref "X-WEST") (pin "7") (pinfunction "7_7") (pintype "bidirectional"))
    )
    (net (code "204") (name "S_I2C_V") (class "Default")
      (node (ref "X-SOUTH") (pin "135") (pinfunction "135_135") (pintype "bidirectional"))
      (node (ref "X-WEST") (pin "9") (pinfunction "9_9") (pintype "bidirectional"))
    )
    (net (code "205") (name "S_SCK") (class "Default")
      (node (ref "X-SOUTH") (pin "144") (pinfunction "144_144") (pintype "bidirectional"))
      (node (ref "X-WEST") (pin "2") (pinfunction "2_2") (pintype "bidirectional"))
    )
    (net (code "206") (name "S_SCL") (class "Default")
      (node (ref "X-SOUTH") (pin "143") (pinfunction "143_143") (pintype "bidirectional"))
      (node (ref "X-WEST") (pin "1") (pinfunction "1_1") (pintype "bidirectional"))
    )
    (net (code "207") (name "S_SDA") (class "Default")
      (node (ref "X-SOUTH") (pin "141") (pinfunction "141_141") (pintype "bidirectional"))
      (node (ref "X-WEST") (pin "3") (pinfunction "3_3") (pintype "bidirectional"))
    )
    (net (code "208") (name "S_SDI") (class "Default")
      (node (ref "X-SOUTH") (pin "140") (pinfunction "140_140") (pintype "bidirectional"))
      (node (ref "X-WEST") (pin "6") (pinfunction "6_6") (pintype "bidirectional"))
    )
    (net (code "209") (name "S_SDO") (class "Default")
      (node (ref "X-SOUTH") (pin "142") (pinfunction "142_142") (pintype "bidirectional"))
      (node (ref "X-WEST") (pin "4") (pinfunction "4_4") (pintype "bidirectional"))
    )
    (net (code "210") (name "S_SPI_EN") (class "Default")
      (node (ref "X-SOUTH") (pin "136") (pinfunction "136_136") (pintype "bidirectional"))
      (node (ref "X-WEST") (pin "8") (pinfunction "8_8") (pintype "bidirectional"))
    )
    (net (code "211") (name "S_SPI_V") (class "Default")
      (node (ref "X-SOUTH") (pin "134") (pinfunction "134_134") (pintype "bidirectional"))
      (node (ref "X-WEST") (pin "10") (pinfunction "10_10") (pintype "bidirectional"))
    )
    (net (code "212") (name "S_VE") (class "Default")
      (node (ref "C7") (pin "1") (pinfunction "1_1") (pintype "passive"))
      (node (ref "SE") (pin "1") (pinfunction "1_1") (pintype "passive"))
      (node (ref "X-SOUTH") (pin "13") (pinfunction "13_13") (pintype "bidirectional"))
      (node (ref "X-SOUTH") (pin "19") (pinfunction "19_19") (pintype "bidirectional"))
      (node (ref "X-SOUTH") (pin "31") (pinfunction "31_31") (pintype "bidirectional"))
      (node (ref "X-SOUTH") (pin "37") (pinfunction "37_37") (pintype "bidirectional"))
    )
    (net (code "213") (name "S_VE_CV") (class "Default")
      (node (ref "X-EAST") (pin "100") (pinfunction "100_100") (pintype "bidirectional"))
      (node (ref "X-SOUTH") (pin "2") (pinfunction "2_2") (pintype "bidirectional"))
    )
    (net (code "214") (name "S_VE_OV") (class "Default")
      (node (ref "X-EAST") (pin "99") (pinfunction "99_99") (pintype "bidirectional"))
      (node (ref "X-SOUTH") (pin "1") (pinfunction "1_1") (pintype "bidirectional"))
    )
    (net (code "215") (name "S_VE_RS") (class "Default")
      (node (ref "X-EAST") (pin "84") (pinfunction "84_84") (pintype "bidirectional"))
      (node (ref "X-SOUTH") (pin "25") (pinfunction "25_25") (pintype "bidirectional"))
    )
    (net (code "216") (name "S_VE_UV") (class "Default")
      (node (ref "X-EAST") (pin "89") (pinfunction "89_89") (pintype "bidirectional"))
      (node (ref "X-SOUTH") (pin "7") (pinfunction "7_7") (pintype "bidirectional"))
    )
    (net (code "217") (name "S_VS") (class "Default")
      (node (ref "C6") (pin "1") (pinfunction "1_1") (pintype "passive"))
      (node (ref "SW") (pin "1") (pinfunction "1_1") (pintype "passive"))
      (node (ref "X-SOUTH") (pin "49") (pinfunction "49_49") (pintype "bidirectional"))
      (node (ref "X-SOUTH") (pin "55") (pinfunction "55_55") (pintype "bidirectional"))
      (node (ref "X-SOUTH") (pin "61") (pinfunction "61_61") (pintype "bidirectional"))
      (node (ref "X-SOUTH") (pin "67") (pinfunction "67_67") (pintype "bidirectional"))
      (node (ref "X-SOUTH") (pin "79") (pinfunction "79_79") (pintype "bidirectional"))
      (node (ref "X-SOUTH") (pin "85") (pinfunction "85_85") (pintype "bidirectional"))
      (node (ref "X-SOUTH") (pin "91") (pinfunction "91_91") (pintype "bidirectional"))
      (node (ref "X-SOUTH") (pin "97") (pinfunction "97_97") (pintype "bidirectional"))
    )
    (net (code "218") (name "S_VS_CV") (class "Default")
      (node (ref "X-EAST") (pin "98") (pinfunction "98_98") (pintype "bidirectional"))
      (node (ref "X-SOUTH") (pin "4") (pinfunction "4_4") (pintype "bidirectional"))
    )
    (net (code "219") (name "S_VS_OV") (class "Default")
      (node (ref "X-EAST") (pin "97") (pinfunction "97_97") (pintype "bidirectional"))
      (node (ref "X-SOUTH") (pin "3") (pinfunction "3_3") (pintype "bidirectional"))
    )
    (net (code "220") (name "S_VS_RS") (class "Default")
      (node (ref "X-EAST") (pin "86") (pinfunction "86_86") (pintype "bidirectional"))
      (node (ref "X-SOUTH") (pin "73") (pinfunction "73_73") (pintype "bidirectional"))
    )
    (net (code "221") (name "S_VS_UV") (class "Default")
      (node (ref "X-EAST") (pin "87") (pinfunction "87_87") (pintype "bidirectional"))
      (node (ref "X-SOUTH") (pin "9") (pinfunction "9_9") (pintype "bidirectional"))
    )
    (net (code "222") (name "S_VW") (class "Default")
      (node (ref "C2") (pin "1") (pinfunction "1_1") (pintype "passive"))
      (node (ref "SW") (pin "2") (pinfunction "2_2") (pintype "passive"))
      (node (ref "X-SOUTH") (pin "109") (pinfunction "109_109") (pintype "bidirectional"))
      (node (ref "X-SOUTH") (pin "115") (pinfunction "115_115") (pintype "bidirectional"))
      (node (ref "X-SOUTH") (pin "127") (pinfunction "127_127") (pintype "bidirectional"))
      (node (ref "X-SOUTH") (pin "133") (pinfunction "133_133") (pintype "bidirectional"))
    )
    (net (code "223") (name "S_VW_CV") (class "Default")
      (node (ref "X-EAST") (pin "96") (pinfunction "96_96") (pintype "bidirectional"))
      (node (ref "X-SOUTH") (pin "6") (pinfunction "6_6") (pintype "bidirectional"))
    )
    (net (code "224") (name "S_VW_OV") (class "Default")
      (node (ref "X-EAST") (pin "95") (pinfunction "95_95") (pintype "bidirectional"))
      (node (ref "X-SOUTH") (pin "5") (pinfunction "5_5") (pintype "bidirectional"))
    )
    (net (code "225") (name "S_VW_RS") (class "Default")
      (node (ref "X-EAST") (pin "88") (pinfunction "88_88") (pintype "bidirectional"))
      (node (ref "X-SOUTH") (pin "121") (pinfunction "121_121") (pintype "bidirectional"))
    )
    (net (code "226") (name "S_VW_UV") (class "Default")
      (node (ref "X-EAST") (pin "85") (pinfunction "85_85") (pintype "bidirectional"))
      (node (ref "X-SOUTH") (pin "11") (pinfunction "11_11") (pintype "bidirectional"))
    )
    (net (code "227") (name "TCK") (class "Default")
      (node (ref "X-WEST") (pin "12") (pinfunction "12_12") (pintype "bidirectional"))
    )
    (net (code "228") (name "TDI") (class "Default")
      (node (ref "X-WEST") (pin "16") (pinfunction "16_16") (pintype "bidirectional"))
    )
    (net (code "229") (name "TDIG1") (class "Default")
      (node (ref "X-EAST") (pin "18") (pinfunction "18_18") (pintype "bidirectional"))
      (node (ref "X-NORTH") (pin "123") (pinfunction "123_123") (pintype "bidirectional"))
    )
    (net (code "230") (name "TDIG2") (class "Default")
      (node (ref "X-NORTH") (pin "130") (pinfunction "130_130") (pintype "bidirectional"))
    )
    (net (code "231") (name "TDO") (class "Default")
      (node (ref "X-WEST") (pin "18") (pinfunction "18_18") (pintype "bidirectional"))
    )
    (net (code "232") (name "TMS") (class "Default")
      (node (ref "X-WEST") (pin "14") (pinfunction "14_14") (pintype "bidirectional"))
    )
    (net (code "233") (name "TP9") (class "Default")
      (node (ref "X-NORTH") (pin "119") (pinfunction "119_119") (pintype "bidirectional"))
    )
    (net (code "234") (name "T_EXP1") (class "Default")
      (node (ref "X-EAST") (pin "12") (pinfunction "12_12") (pintype "bidirectional"))
      (node (ref "X-NORTH") (pin "131") (pinfunction "131_131") (pintype "bidirectional"))
    )
    (net (code "235") (name "T_EXP2") (class "Default")
      (node (ref "X-EAST") (pin "16") (pinfunction "16_16") (pintype "bidirectional"))
      (node (ref "X-NORTH") (pin "117") (pinfunction "117_117") (pintype "bidirectional"))
    )
    (net (code "236") (name "W_EN") (class "Default")
      (node (ref "X-WEST") (pin "19") (pinfunction "19_19") (pintype "bidirectional"))
    )
    (net (code "237") (name "W_I2C_EN") (class "Default")
      (node (ref "X-WEST") (pin "13") (pinfunction "13_13") (pintype "bidirectional"))
    )
    (net (code "238") (name "W_I2C_V") (class "Default")
      (node (ref "X-WEST") (pin "11") (pinfunction "11_11") (pintype "bidirectional"))
    )
    (net (code "239") (name "W_SCL") (class "Default")
      (node (ref "X-WEST") (pin "15") (pinfunction "15_15") (pintype "bidirectional"))
    )
    (net (code "240") (name "W_SDA") (class "Default")
      (node (ref "X-WEST") (pin "17") (pinfunction "17_17") (pintype "bidirectional"))
    )
    (net (code "241") (name "W_VW") (class "Default")
      (node (ref "C8") (pin "1") (pinfunction "1_1") (pintype "passive"))
      (node (ref "NW") (pin "2") (pinfunction "2_2") (pintype "passive"))
    )
    (net (code "242") (name "W_VW_CV") (class "Default")
      (node (ref "X-WEST") (pin "90") (pinfunction "90_90") (pintype "bidirectional"))
    )
    (net (code "243") (name "W_VW_OV") (class "Default")
      (node (ref "X-WEST") (pin "93") (pinfunction "93_93") (pintype "bidirectional"))
    )
    (net (code "244") (name "W_VW_UV") (class "Default")
      (node (ref "X-WEST") (pin "91") (pinfunction "91_91") (pintype "bidirectional"))
    )
    (net (code "245") (name "unconnected-(X-EAST-PadM1)") (class "Default")
      (node (ref "X-EAST") (pin "M1") (pinfunction "M1_M1") (pintype "bidirectional"))
    )
    (net (code "246") (name "unconnected-(X-EAST-PadM2)") (class "Default")
      (node (ref "X-EAST") (pin "M2") (pinfunction "M2_M2") (pintype "bidirectional"))
    )
    (net (code "247") (name "unconnected-(X-NORTH-PadM1)") (class "Default")
      (node (ref "X-NORTH") (pin "M1") (pinfunction "M1_M1") (pintype "bidirectional"))
    )
    (net (code "248") (name "unconnected-(X-NORTH-PadM2)") (class "Default")
      (node (ref "X-NORTH") (pin "M2") (pinfunction "M2_M2") (pintype "bidirectional"))
    )
    (net (code "249") (name "unconnected-(X-SOUTH-PadM1)") (class "Default")
      (node (ref "X-SOUTH") (pin "M1") (pinfunction "M1_M1") (pintype "bidirectional"))
    )
    (net (code "250") (name "unconnected-(X-SOUTH-PadM2)") (class "Default")
      (node (ref "X-SOUTH") (pin "M2") (pinfunction "M2_M2") (pintype "bidirectional"))
    )
    (net (code "251") (name "unconnected-(X-WEST-PadM1)") (class "Default")
      (node (ref "X-WEST") (pin "M1") (pinfunction "M1_M1") (pintype "bidirectional"))
    )
    (net (code "252") (name "unconnected-(X-WEST-PadM2)") (class "Default")
      (node (ref "X-WEST") (pin "M2") (pinfunction "M2_M2") (pintype "bidirectional"))
    )
  )
)
